# Schematic.net
KiCad netlist of a schematic drawn in EAGLE
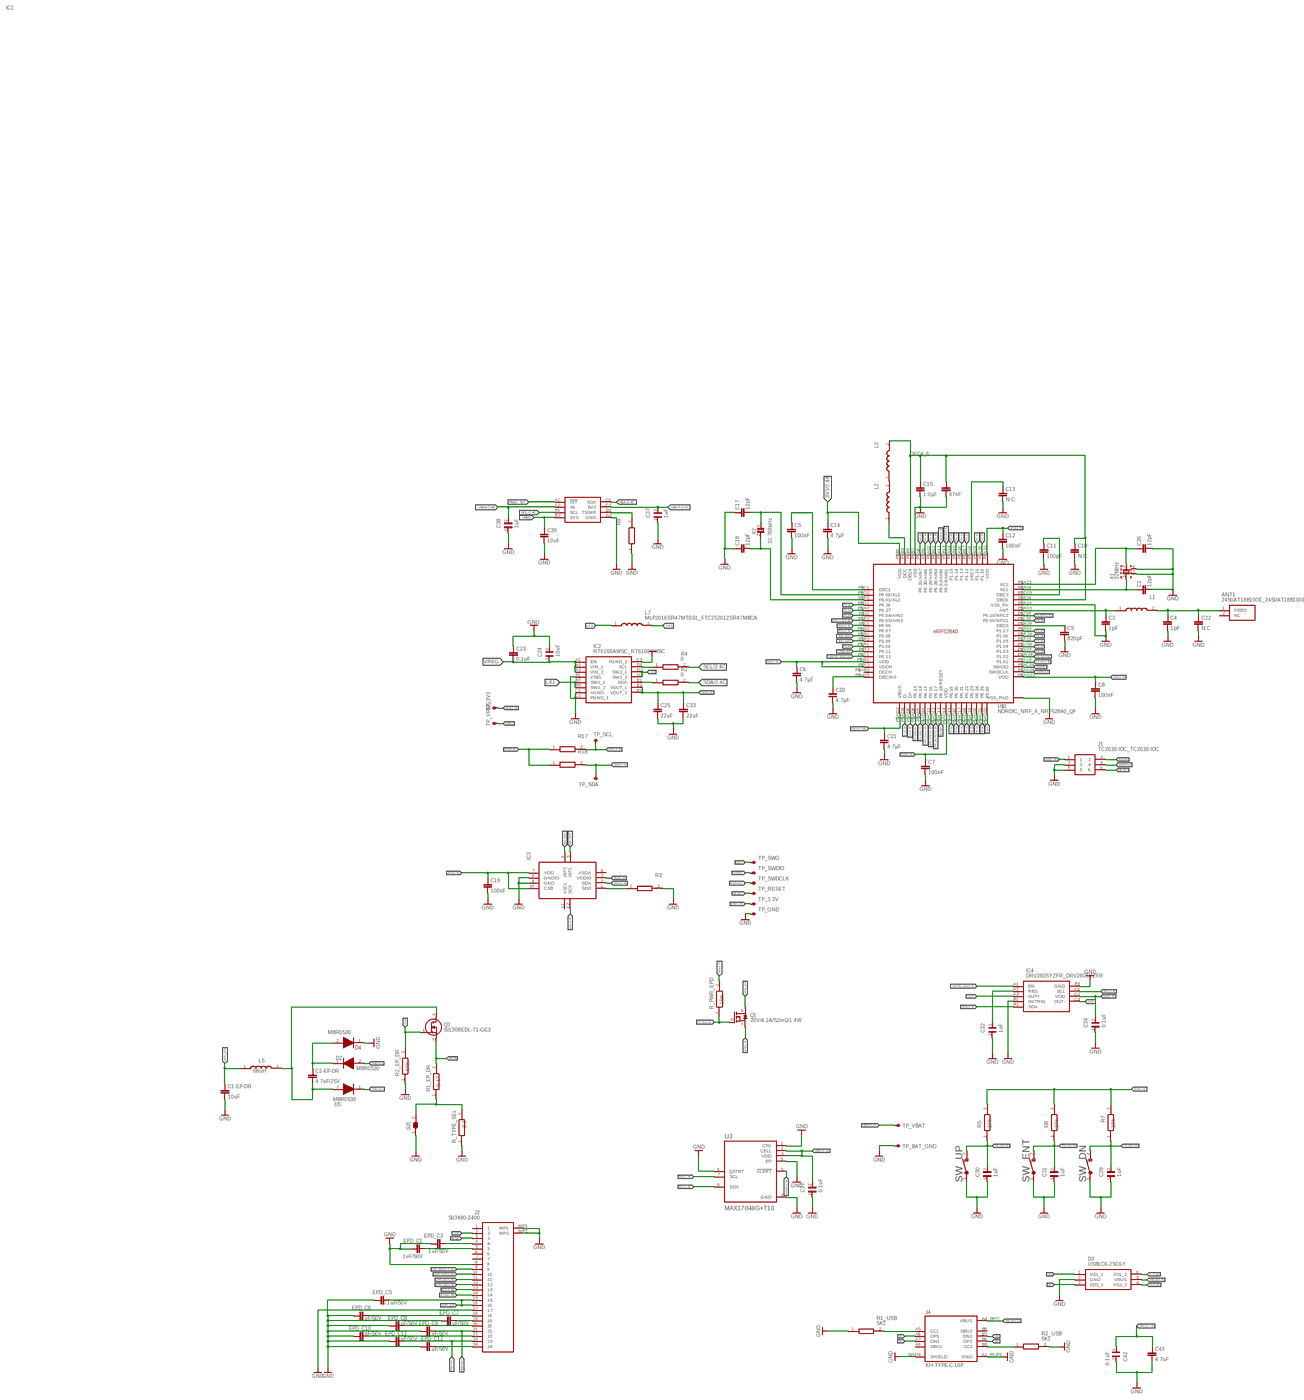
[diagram p0: schematic, sheet 1, overview]
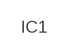
[diagram p1: schematic, sheet 1, part 1 of 4]
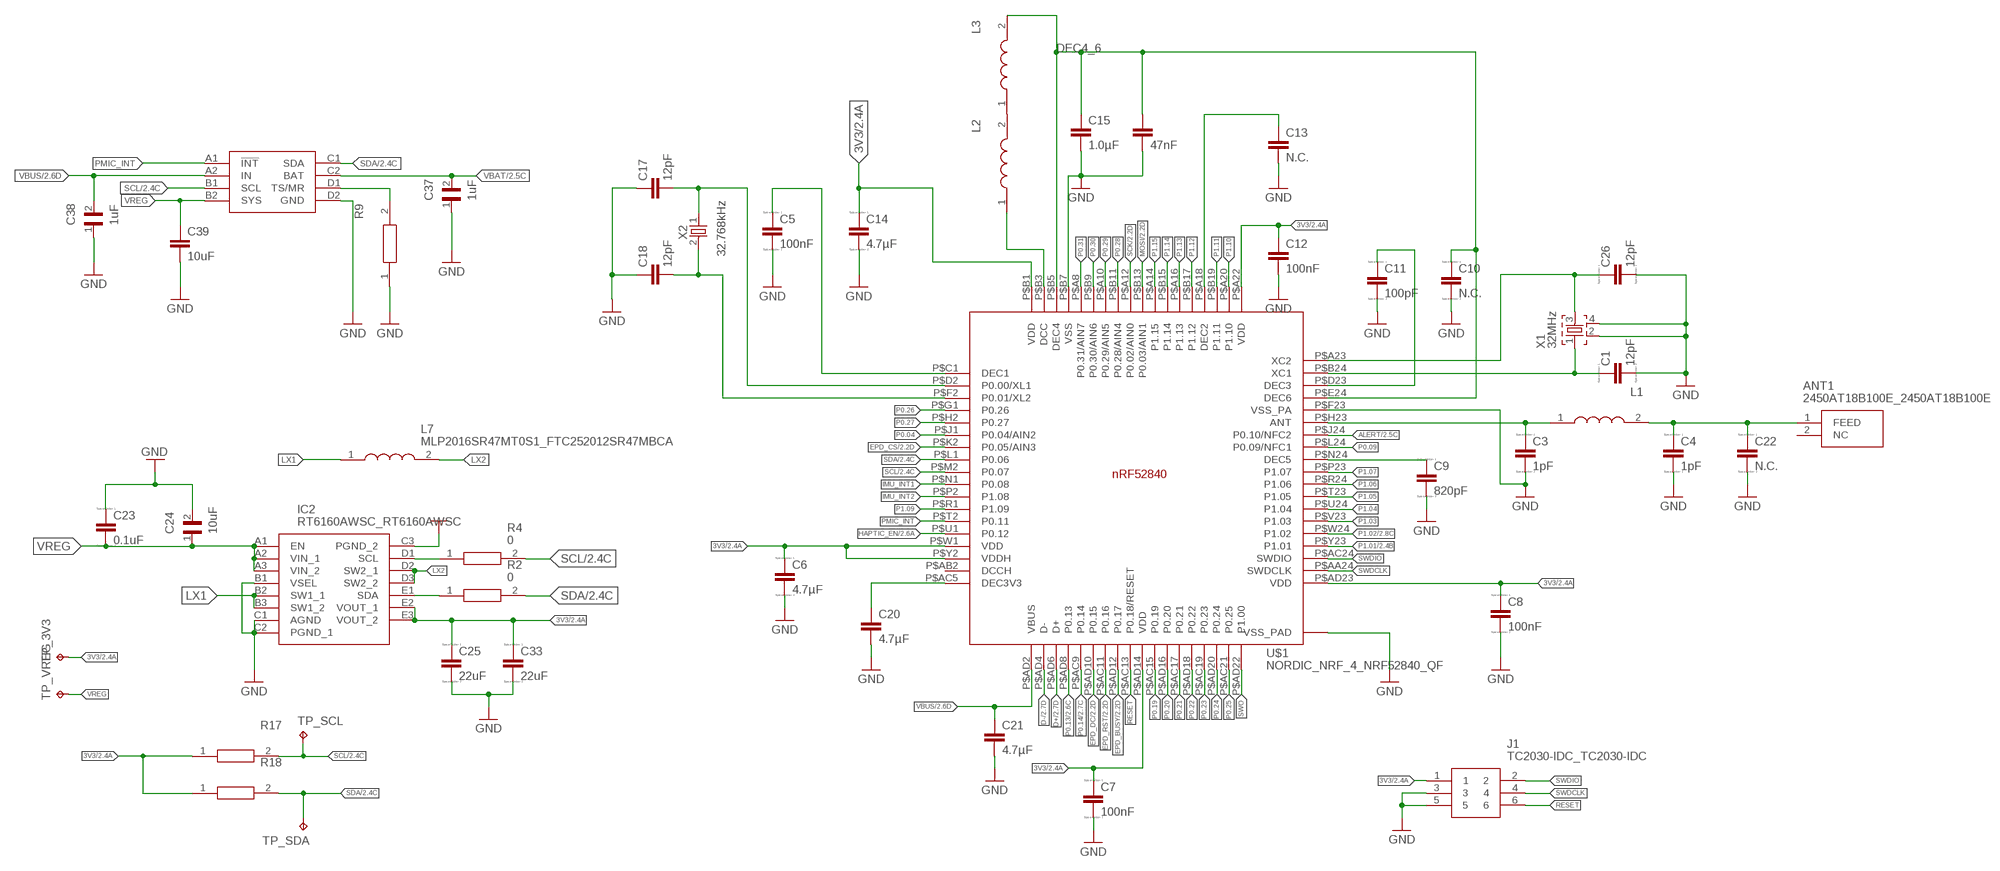
[diagram p2: schematic, sheet 1, part 2 of 4]
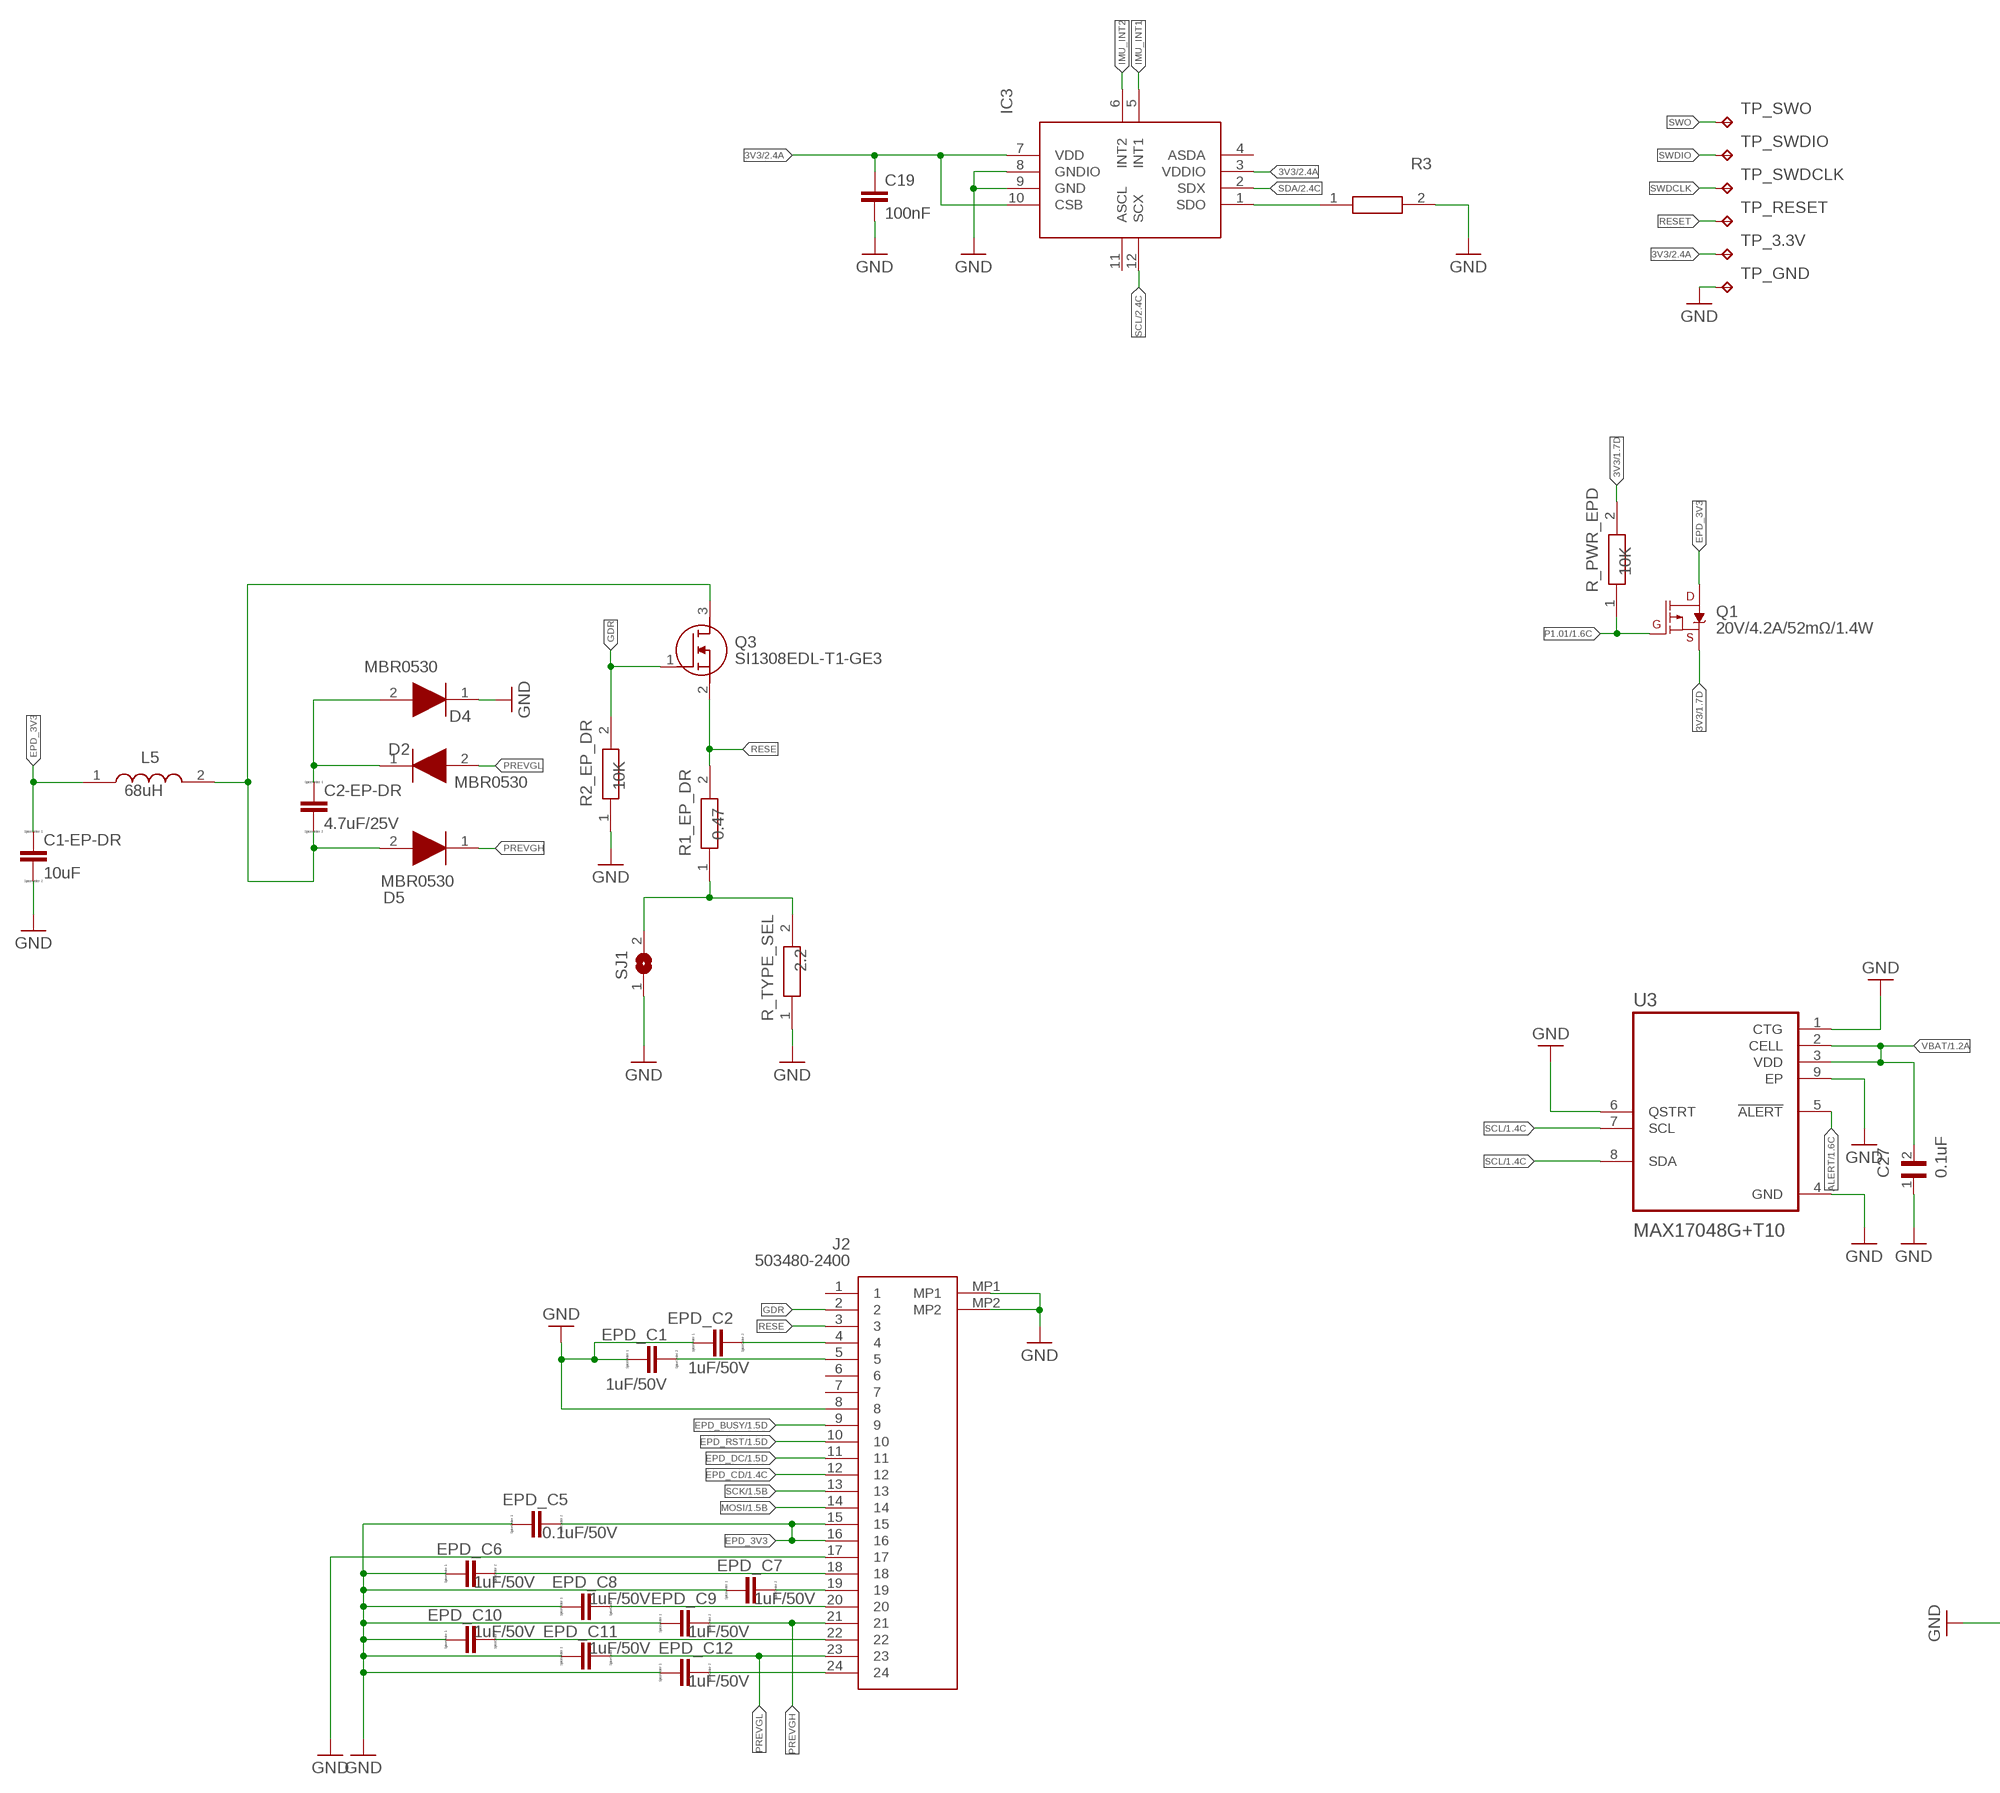
[diagram p3: schematic, sheet 1, part 3 of 4]
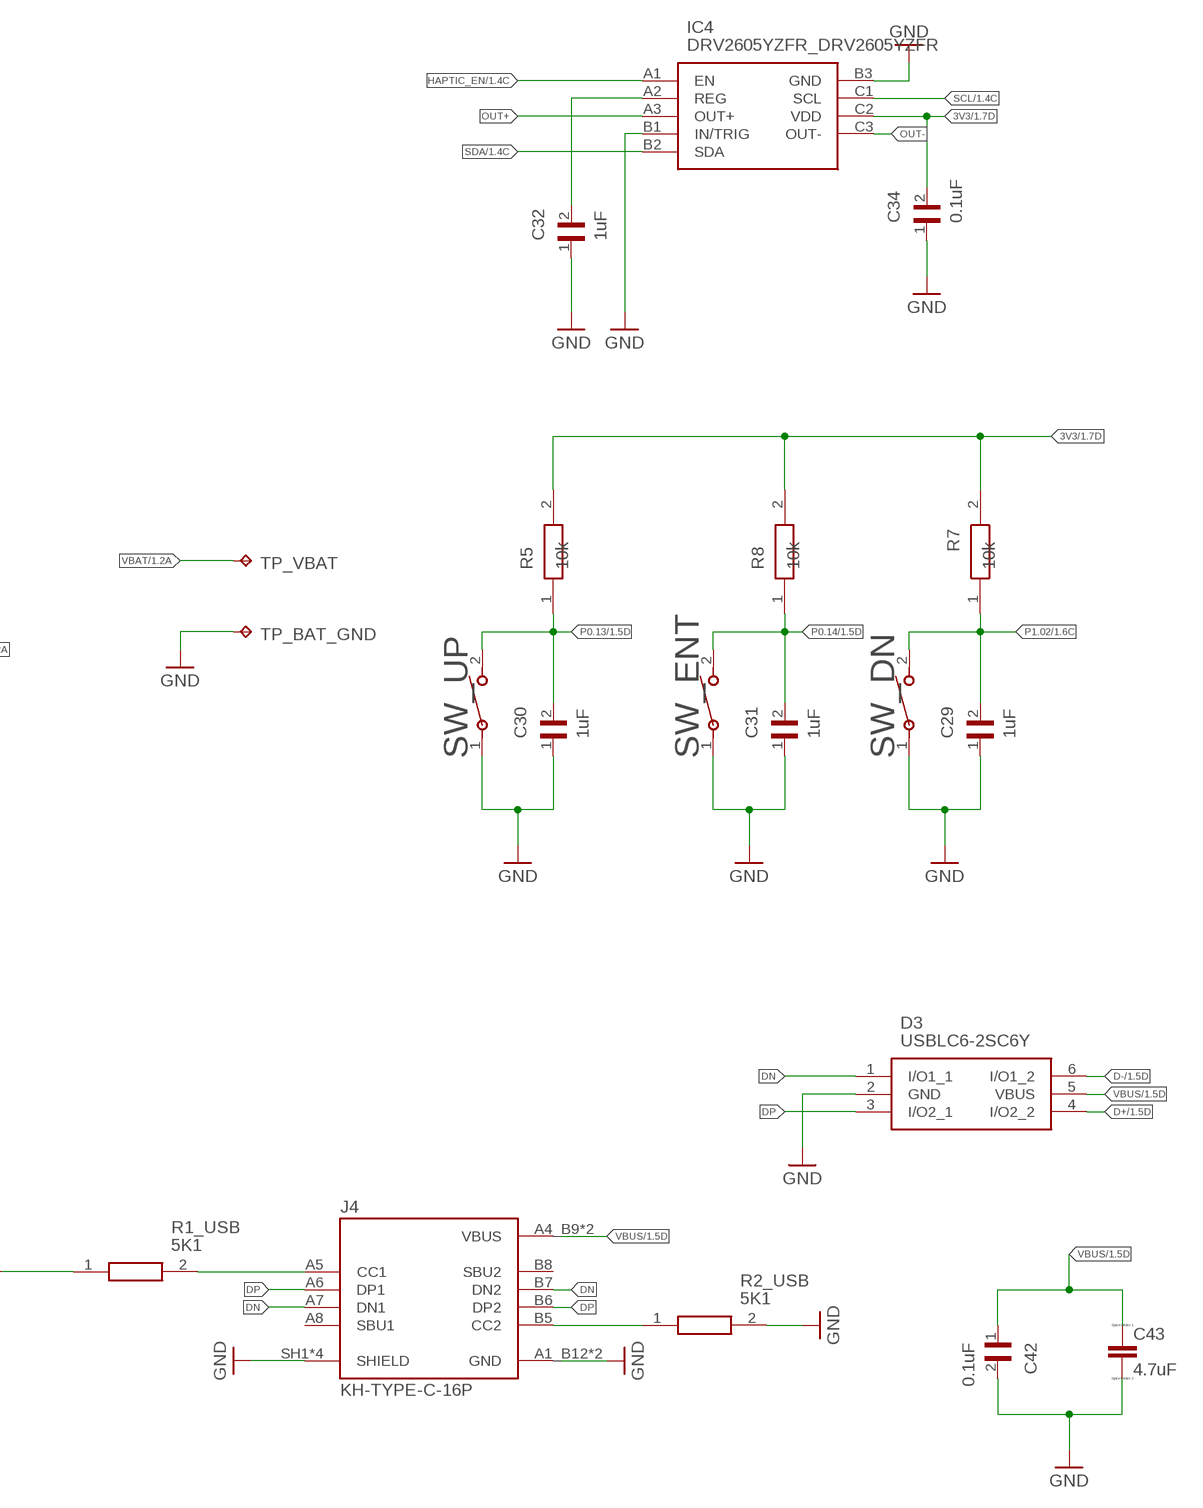
[diagram p4: schematic, sheet 1, part 4 of 4]

(export (version "E")
  (design (tool "Eeschema 10.0.6"))
  (components
    (comp (ref "ANT1")
      (value "2450AT18B100E_2450AT18B100E")
      (footprint "eagle-import:2450AT18B100E_ANTC3216X140N")
      (fields
        (field (name "ARROW_PART_NUMBER") "2450AT18B100E")
        (field (name "MOUSER_PART_NUMBER") "609-2450AT18B100E")
      )
      (libsource (lib "eagle-import") (part "2450AT18B100E_2450AT18B100E"))
    )
    (comp (ref "C1")
      (value "12pF")
      (footprint "eagle-import:ESP32_C6_LIBRARY_1_ESP32_WROVER_EAGLE-LTSPICE_C0402")
      (libsource (lib "eagle-import") (part "ESP32_C6_LIBRARY_1_ESP32_WROVER_EAGLE-LTSPICE_CC0402"))
    )
    (comp (ref "C1-EP-DR")
      (value "10uF")
      (footprint "eagle-import:ESP32_C6_LIBRARY_1_ESP32_WROVER_EAGLE-LTSPICE_C0402")
      (libsource (lib "eagle-import") (part "ESP32_C6_LIBRARY_1_ESP32_WROVER_EAGLE-LTSPICE_CC0402"))
    )
    (comp (ref "C2-EP-DR")
      (value "4.7uF/25V")
      (footprint "eagle-import:ESP32_C6_LIBRARY_1_ESP32_WROVER_EAGLE-LTSPICE_C0402")
      (libsource (lib "eagle-import") (part "ESP32_C6_LIBRARY_1_ESP32_WROVER_EAGLE-LTSPICE_CC0402"))
    )
    (comp (ref "C3")
      (value "1pF")
      (footprint "eagle-import:ESP32_C6_LIBRARY_1_ESP32_WROVER_EAGLE-LTSPICE_C0402")
      (libsource (lib "eagle-import") (part "ESP32_C6_LIBRARY_1_ESP32_WROVER_EAGLE-LTSPICE_CC0402"))
    )
    (comp (ref "C4")
      (value "1pF")
      (footprint "eagle-import:ESP32_C6_LIBRARY_1_ESP32_WROVER_EAGLE-LTSPICE_C0402")
      (libsource (lib "eagle-import") (part "ESP32_C6_LIBRARY_1_ESP32_WROVER_EAGLE-LTSPICE_CC0402"))
    )
    (comp (ref "C5")
      (value "100nF")
      (footprint "eagle-import:ESP32_C6_LIBRARY_1_ESP32_WROVER_EAGLE-LTSPICE_C0402")
      (libsource (lib "eagle-import") (part "ESP32_C6_LIBRARY_1_ESP32_WROVER_EAGLE-LTSPICE_CC0402"))
    )
    (comp (ref "C6")
      (value "4.7µF")
      (footprint "eagle-import:ESP32_C6_LIBRARY_1_ESP32_WROVER_EAGLE-LTSPICE_C0402")
      (libsource (lib "eagle-import") (part "ESP32_C6_LIBRARY_1_ESP32_WROVER_EAGLE-LTSPICE_CC0402"))
    )
    (comp (ref "C7")
      (value "100nF")
      (footprint "eagle-import:ESP32_C6_LIBRARY_1_ESP32_WROVER_EAGLE-LTSPICE_C0402")
      (libsource (lib "eagle-import") (part "ESP32_C6_LIBRARY_1_ESP32_WROVER_EAGLE-LTSPICE_CC0402"))
    )
    (comp (ref "C8")
      (value "100nF")
      (footprint "eagle-import:ESP32_C6_LIBRARY_1_ESP32_WROVER_EAGLE-LTSPICE_C0402")
      (libsource (lib "eagle-import") (part "ESP32_C6_LIBRARY_1_ESP32_WROVER_EAGLE-LTSPICE_CC0402"))
    )
    (comp (ref "C9")
      (value "820pF")
      (footprint "eagle-import:ESP32_C6_LIBRARY_1_ESP32_WROVER_EAGLE-LTSPICE_C0402")
      (libsource (lib "eagle-import") (part "ESP32_C6_LIBRARY_1_ESP32_WROVER_EAGLE-LTSPICE_CC0402"))
    )
    (comp (ref "C10")
      (value "N.C.")
      (footprint "eagle-import:ESP32_C6_LIBRARY_1_ESP32_WROVER_EAGLE-LTSPICE_C0402")
      (libsource (lib "eagle-import") (part "ESP32_C6_LIBRARY_1_ESP32_WROVER_EAGLE-LTSPICE_CC0402"))
    )
    (comp (ref "C11")
      (value "100pF")
      (footprint "eagle-import:ESP32_C6_LIBRARY_1_ESP32_WROVER_EAGLE-LTSPICE_C0402")
      (libsource (lib "eagle-import") (part "ESP32_C6_LIBRARY_1_ESP32_WROVER_EAGLE-LTSPICE_CC0402"))
    )
    (comp (ref "C12")
      (value "100nF")
      (footprint "eagle-import:PERFECT_0402_0402")
      (libsource (lib "eagle-import") (part "PERFECT_0402_CAP_0402"))
    )
    (comp (ref "C13")
      (value "N.C.")
      (footprint "eagle-import:PERFECT_0402_0402")
      (libsource (lib "eagle-import") (part "PERFECT_0402_CAP_0402"))
    )
    (comp (ref "C14")
      (value "4.7µF")
      (footprint "eagle-import:ESP32_C6_LIBRARY_1_ESP32_WROVER_EAGLE-LTSPICE_C0402")
      (libsource (lib "eagle-import") (part "ESP32_C6_LIBRARY_1_ESP32_WROVER_EAGLE-LTSPICE_CC0402"))
    )
    (comp (ref "C15")
      (value "1.0µF")
      (footprint "eagle-import:PERFECT_0402_0402")
      (libsource (lib "eagle-import") (part "PERFECT_0402_CAP_0402"))
    )
    (comp (ref "C16")
      (value "47nF")
      (footprint "eagle-import:PERFECT_0402_0402")
      (libsource (lib "eagle-import") (part "PERFECT_0402_CAP_0402"))
    )
    (comp (ref "C17")
      (value "12pF")
      (footprint "eagle-import:PERFECT_0402_0402")
      (libsource (lib "eagle-import") (part "PERFECT_0402_CAP_0402"))
    )
    (comp (ref "C18")
      (value "12pF")
      (footprint "eagle-import:PERFECT_0402_0402")
      (libsource (lib "eagle-import") (part "PERFECT_0402_CAP_0402"))
    )
    (comp (ref "C19")
      (value "100nF")
      (footprint "eagle-import:PERFECT_0402_0402")
      (libsource (lib "eagle-import") (part "PERFECT_0402_CAP_0402"))
    )
    (comp (ref "C20")
      (value "4.7µF")
      (footprint "eagle-import:PERFECT_0402_0402")
      (libsource (lib "eagle-import") (part "PERFECT_0402_CAP_0402"))
    )
    (comp (ref "C21")
      (value "4.7µF")
      (footprint "eagle-import:PERFECT_0402_0402")
      (libsource (lib "eagle-import") (part "PERFECT_0402_CAP_0402"))
    )
    (comp (ref "C22")
      (value "N.C.")
      (footprint "eagle-import:ESP32_C6_LIBRARY_1_ESP32_WROVER_EAGLE-LTSPICE_C0402")
      (libsource (lib "eagle-import") (part "ESP32_C6_LIBRARY_1_ESP32_WROVER_EAGLE-LTSPICE_CC0402"))
    )
    (comp (ref "C23")
      (value "0.1uF")
      (footprint "eagle-import:ESP32_C6_LIBRARY_1_ESP32_WROVER_EAGLE-LTSPICE_C0402")
      (libsource (lib "eagle-import") (part "ESP32_C6_LIBRARY_1_ESP32_WROVER_EAGLE-LTSPICE_CC0402"))
    )
    (comp (ref "C24")
      (value "10uF")
      (footprint "eagle-import:GRM011R60J152KE01L_2_CAPC0201X13N")
      (fields (field (name "MF") "Murata") (field (name "MP") "GRM011R60J152KE01L"))
      (libsource (lib "eagle-import") (part "GRM011R60J152KE01L_2_GRM011R60J152KE01L"))
    )
    (comp (ref "C25")
      (value "22uF")
      (footprint "eagle-import:ESP32_C6_LIBRARY_1_ESP32_WROVER_EAGLE-LTSPICE_C0402")
      (libsource (lib "eagle-import") (part "ESP32_C6_LIBRARY_1_ESP32_WROVER_EAGLE-LTSPICE_CC0402"))
    )
    (comp (ref "C26")
      (value "12pF")
      (footprint "eagle-import:ESP32_C6_LIBRARY_1_ESP32_WROVER_EAGLE-LTSPICE_C0402")
      (libsource (lib "eagle-import") (part "ESP32_C6_LIBRARY_1_ESP32_WROVER_EAGLE-LTSPICE_CC0402"))
    )
    (comp (ref "C27")
      (value "0.1uF")
      (footprint "eagle-import:GRM011R60J152KE01L_2_CAPC0201X13N")
      (fields (field (name "MF") "Murata") (field (name "MP") "GRM011R60J152KE01L"))
      (libsource (lib "eagle-import") (part "GRM011R60J152KE01L_2_GRM011R60J152KE01L"))
    )
    (comp (ref "C29")
      (value "1uF")
      (footprint "eagle-import:GRM011R60J152KE01L_2_CAPC0201X13N")
      (fields (field (name "MF") "Murata") (field (name "MP") "GRM011R60J152KE01L"))
      (libsource (lib "eagle-import") (part "GRM011R60J152KE01L_2_GRM011R60J152KE01L"))
    )
    (comp (ref "C30")
      (value "1uF")
      (footprint "eagle-import:GRM011R60J152KE01L_2_CAPC0201X13N")
      (fields (field (name "MF") "Murata") (field (name "MP") "GRM011R60J152KE01L"))
      (libsource (lib "eagle-import") (part "GRM011R60J152KE01L_2_GRM011R60J152KE01L"))
    )
    (comp (ref "C31")
      (value "1uF")
      (footprint "eagle-import:GRM011R60J152KE01L_2_CAPC0201X13N")
      (fields (field (name "MF") "Murata") (field (name "MP") "GRM011R60J152KE01L"))
      (libsource (lib "eagle-import") (part "GRM011R60J152KE01L_2_GRM011R60J152KE01L"))
    )
    (comp (ref "C32")
      (value "1uF")
      (footprint "eagle-import:GRM011R60J152KE01L_2_CAPC0201X13N")
      (fields (field (name "MF") "Murata") (field (name "MP") "GRM011R60J152KE01L"))
      (libsource (lib "eagle-import") (part "GRM011R60J152KE01L_2_GRM011R60J152KE01L"))
    )
    (comp (ref "C33")
      (value "22uF")
      (footprint "eagle-import:ESP32_C6_LIBRARY_1_ESP32_WROVER_EAGLE-LTSPICE_C0402")
      (libsource (lib "eagle-import") (part "ESP32_C6_LIBRARY_1_ESP32_WROVER_EAGLE-LTSPICE_CC0402"))
    )
    (comp (ref "C34")
      (value "0.1uF")
      (footprint "eagle-import:GRM011R60J152KE01L_2_CAPC0201X13N")
      (fields (field (name "MF") "Murata") (field (name "MP") "GRM011R60J152KE01L"))
      (libsource (lib "eagle-import") (part "GRM011R60J152KE01L_2_GRM011R60J152KE01L"))
    )
    (comp (ref "C37")
      (value "1uF")
      (footprint "eagle-import:GRM011R60J152KE01L_1_0201")
      (libsource (lib "eagle-import") (part "GRM011R60J152KE01L_1_GRM011R60J152KE01L"))
    )
    (comp (ref "C38")
      (value "1uF")
      (footprint "eagle-import:GRM011R60J152KE01L_1_0201")
      (libsource (lib "eagle-import") (part "GRM011R60J152KE01L_1_GRM011R60J152KE01L"))
    )
    (comp (ref "C39")
      (value "10uF")
      (footprint "eagle-import:PERFECT_0402_0402")
      (libsource (lib "eagle-import") (part "PERFECT_0402_CAP_0402"))
    )
    (comp (ref "C42")
      (value "0.1uF")
      (footprint "eagle-import:GRM011R60J152KE01L_2_CAPC0201X13N")
      (fields (field (name "MF") "Murata") (field (name "MP") "GRM011R60J152KE01L"))
      (libsource (lib "eagle-import") (part "GRM011R60J152KE01L_2_GRM011R60J152KE01L"))
    )
    (comp (ref "C43")
      (value "4.7uF")
      (footprint "eagle-import:ESP32_C6_LIBRARY_1_ESP32_WROVER_EAGLE-LTSPICE_C0402")
      (libsource (lib "eagle-import") (part "ESP32_C6_LIBRARY_1_ESP32_WROVER_EAGLE-LTSPICE_CC0402"))
    )
    (comp (ref "D2")
      (value "MBR0530")
      (footprint "eagle-import:ESP32_C6_LIBRARY_5_SOD3716X135N")
      (fields (field (name "MF") "ON Semiconductor"))
      (libsource (lib "eagle-import") (part "ESP32_C6_LIBRARY_5_MBR0530"))
    )
    (comp (ref "D3")
      (value "USBLC6-2SC6Y")
      (footprint "eagle-import:ESP32_C6_LIBRARY_3_SOT95P280X145-6N")
      (fields (field (name "MF") "STMicroelectronics"))
      (libsource (lib "eagle-import") (part "ESP32_C6_LIBRARY_3_USBLC6-2SC6Y"))
    )
    (comp (ref "D4")
      (value "MBR0530")
      (footprint "eagle-import:ESP32_C6_LIBRARY_5_SOD3716X135N")
      (fields (field (name "MF") "ON Semiconductor"))
      (libsource (lib "eagle-import") (part "ESP32_C6_LIBRARY_5_MBR0530"))
    )
    (comp (ref "D5")
      (value "MBR0530")
      (footprint "eagle-import:ESP32_C6_LIBRARY_5_SOD3716X135N")
      (fields (field (name "MF") "ON Semiconductor"))
      (libsource (lib "eagle-import") (part "ESP32_C6_LIBRARY_5_MBR0530"))
    )
    (comp (ref "EPD_C1")
      (value "1uF/50V")
      (footprint "eagle-import:ESP32_C6_LIBRARY_1_ESP32_WROVER_EAGLE-LTSPICE_C0402")
      (libsource (lib "eagle-import") (part "ESP32_C6_LIBRARY_1_ESP32_WROVER_EAGLE-LTSPICE_CC0402"))
    )
    (comp (ref "EPD_C2")
      (value "1uF/50V")
      (footprint "eagle-import:ESP32_C6_LIBRARY_1_ESP32_WROVER_EAGLE-LTSPICE_C0402")
      (libsource (lib "eagle-import") (part "ESP32_C6_LIBRARY_1_ESP32_WROVER_EAGLE-LTSPICE_CC0402"))
    )
    (comp (ref "EPD_C5")
      (value "0.1uF/50V")
      (footprint "eagle-import:ESP32_C6_LIBRARY_1_ESP32_WROVER_EAGLE-LTSPICE_C0402")
      (libsource (lib "eagle-import") (part "ESP32_C6_LIBRARY_1_ESP32_WROVER_EAGLE-LTSPICE_CC0402"))
    )
    (comp (ref "EPD_C6")
      (value "1uF/50V")
      (footprint "eagle-import:ESP32_C6_LIBRARY_1_ESP32_WROVER_EAGLE-LTSPICE_C0402")
      (libsource (lib "eagle-import") (part "ESP32_C6_LIBRARY_1_ESP32_WROVER_EAGLE-LTSPICE_CC0402"))
    )
    (comp (ref "EPD_C7")
      (value "1uF/50V")
      (footprint "eagle-import:ESP32_C6_LIBRARY_1_ESP32_WROVER_EAGLE-LTSPICE_C0402")
      (libsource (lib "eagle-import") (part "ESP32_C6_LIBRARY_1_ESP32_WROVER_EAGLE-LTSPICE_CC0402"))
    )
    (comp (ref "EPD_C8")
      (value "1uF/50V")
      (footprint "eagle-import:ESP32_C6_LIBRARY_1_ESP32_WROVER_EAGLE-LTSPICE_C0402")
      (libsource (lib "eagle-import") (part "ESP32_C6_LIBRARY_1_ESP32_WROVER_EAGLE-LTSPICE_CC0402"))
    )
    (comp (ref "EPD_C9")
      (value "1uF/50V")
      (footprint "eagle-import:ESP32_C6_LIBRARY_1_ESP32_WROVER_EAGLE-LTSPICE_C0402")
      (libsource (lib "eagle-import") (part "ESP32_C6_LIBRARY_1_ESP32_WROVER_EAGLE-LTSPICE_CC0402"))
    )
    (comp (ref "EPD_C10")
      (value "1uF/50V")
      (footprint "eagle-import:ESP32_C6_LIBRARY_1_ESP32_WROVER_EAGLE-LTSPICE_C0402")
      (libsource (lib "eagle-import") (part "ESP32_C6_LIBRARY_1_ESP32_WROVER_EAGLE-LTSPICE_CC0402"))
    )
    (comp (ref "EPD_C11")
      (value "1uF/50V")
      (footprint "eagle-import:ESP32_C6_LIBRARY_1_ESP32_WROVER_EAGLE-LTSPICE_C0402")
      (libsource (lib "eagle-import") (part "ESP32_C6_LIBRARY_1_ESP32_WROVER_EAGLE-LTSPICE_CC0402"))
    )
    (comp (ref "EPD_C12")
      (value "1uF/50V")
      (footprint "eagle-import:ESP32_C6_LIBRARY_1_ESP32_WROVER_EAGLE-LTSPICE_C0402")
      (libsource (lib "eagle-import") (part "ESP32_C6_LIBRARY_1_ESP32_WROVER_EAGLE-LTSPICE_CC0402"))
    )
    (comp (ref "IC1")
      (value "BQ25180YBGR_BQ25180YBGR")
      (footprint "eagle-import:BQ25180YBGR_BGA8C40P2X4_100X155X50")
      (fields
        (field (name "ARROW_PART_NUMBER") "BQ25180YBGR")
        (field (name "MOUSER_PART_NUMBER") "595-BQ25180YBGR")
      )
      (libsource (lib "eagle-import") (part "BQ25180YBGR_BQ25180YBGR"))
    )
    (comp (ref "IC2")
      (value "RT6160AWSC_RT6160AWSC")
      (footprint "eagle-import:RT6160AWSC_BGA15C40P3X5_140X230X60")
      (fields
        (field (name "MANUFACTURER_PART_NUMBER") "RT6160AWSC")
        (field (name "MOUSER_PART_NUMBER") "835-RT6160AWSC")
      )
      (libsource (lib "eagle-import") (part "RT6160AWSC_RT6160AWSC"))
    )
    (comp (ref "IC3")
      (value "BMA421_BMA421")
      (footprint "eagle-import:BMA421_BMA421")
      (fields (field (name "ARROW_PART_NUMBER") "BMA421") (field (name "MOUSER_PART_NUMBER") "262-BMA421"))
      (libsource (lib "eagle-import") (part "BMA421_BMA421"))
    )
    (comp (ref "IC4")
      (value "DRV2605YZFR_DRV2605YZFR")
      (footprint "eagle-import:DRV2605YZFR_BGA9C50P3X3_144X144X62")
      (fields (field (name "ARROW_PART_NUMBER") "DRV2605YZFR"))
      (libsource (lib "eagle-import") (part "DRV2605YZFR_DRV2605YZFR"))
    )
    (comp (ref "J1")
      (value "TC2030-IDC_TC2030-IDC")
      (footprint "eagle-import:TC2030-IDC_TC2030IDC")
      (fields (field (name "MANUFACTURER_PART_NUMBER") "TC2030-IDC"))
      (libsource (lib "eagle-import") (part "TC2030-IDC_TC2030-IDC"))
    )
    (comp (ref "J2")
      (value "503480-2400")
      (footprint "eagle-import:503480-2400_5034802400")
      (fields (field (name "MOUSER_PART_NUMBER") "538-503480-2400"))
      (libsource (lib "eagle-import") (part "503480-2400_503480-2400"))
    )
    (comp (ref "J4")
      (value "KH-TYPE-C-16P")
      (footprint "eagle-import:KH-TYPE-C-16P_KINGHELM_KH-TYPE-C-16P")
      (fields (field (name "MF") "kinghelm"))
      (libsource (lib "eagle-import") (part "KH-TYPE-C-16P_KH-TYPE-C-16P"))
    )
    (comp (ref "L1")
      (value "3.9nH")
      (footprint "eagle-import:MLP2016SR47MT0S1_INDC2016X100N")
      (fields (field (name "MANUFACTURER_PART_NUMBER") "FTC252012SR47MBCA"))
      (libsource (lib "eagle-import") (part "MLP2016SR47MT0S1_FTC252012SR47MBCA"))
    )
    (comp (ref "L2")
      (value "10µH")
      (footprint "eagle-import:MLP2016SR47MT0S1_INDC2016X100N")
      (fields (field (name "MANUFACTURER_PART_NUMBER") "FTC252012SR47MBCA"))
      (libsource (lib "eagle-import") (part "MLP2016SR47MT0S1_FTC252012SR47MBCA"))
    )
    (comp (ref "L3")
      (value "15nH")
      (footprint "eagle-import:MLP2016SR47MT0S1_INDC2016X100N")
      (fields (field (name "MANUFACTURER_PART_NUMBER") "FTC252012SR47MBCA"))
      (libsource (lib "eagle-import") (part "MLP2016SR47MT0S1_FTC252012SR47MBCA"))
    )
    (comp (ref "L5")
      (value "68uH")
      (footprint "eagle-import:MLP2016SR47MT0S1_INDC2016X100N")
      (fields (field (name "MANUFACTURER_PART_NUMBER") "FTC252012SR47MBCA"))
      (libsource (lib "eagle-import") (part "MLP2016SR47MT0S1_FTC252012SR47MBCA"))
    )
    (comp (ref "L7")
      (value "MLP2016SR47MT0S1_FTC252012SR47MBCA")
      (footprint "eagle-import:MLP2016SR47MT0S1_INDC2016X100N")
      (fields (field (name "MANUFACTURER_PART_NUMBER") "FTC252012SR47MBCA"))
      (libsource (lib "eagle-import") (part "MLP2016SR47MT0S1_FTC252012SR47MBCA"))
    )
    (comp (ref "Q1")
      (value "20V/4.2A/52mΩ/1.4W")
      (footprint "eagle-import:ESP32_C6_LIBRARY_4_ESP32_C6_LIBRARY_4_ESP32_C6_LIBRARY_4_ESP32_C6_LIBRARY_4_ESP32_WROVER_SPARKFUN-DISCRETESEMI_SOT23-3")
      (libsource (lib "eagle-import") (part "ESP32_C6_LIBRARY_4_ESP32_WROVER_SPARKFUN-DISCRETESEMI_MOSFET_PCH-DMG2305UX-7"))
    )
    (comp (ref "Q3")
      (value "SI1308EDL-T1-GE3")
      (footprint "eagle-import:ESP32_C6_LIBRARY_6_SOT65P210X110-3N")
      (fields (field (name "MF") "Vishay Siliconix"))
      (libsource (lib "eagle-import") (part "ESP32_C6_LIBRARY_6_SI1308EDL-T1-GE3"))
    )
    (comp (ref "R1_EP_DR")
      (value "0.47")
      (footprint "eagle-import:CPF0201D7K68C1_0201")
      (libsource (lib "eagle-import") (part "CPF0201D7K68C1_CPF0201D7K68C1"))
    )
    (comp (ref "R1_USB")
      (value "5K1")
      (footprint "eagle-import:ERA-1AEB3401C_0201")
      (libsource (lib "eagle-import") (part "ERA-1AEB3401C_CPF0201D7K68C1"))
    )
    (comp (ref "R2")
      (value "0")
      (footprint "eagle-import:CPF0201D7K68C1_0201")
      (libsource (lib "eagle-import") (part "CPF0201D7K68C1_CPF0201D7K68C1"))
    )
    (comp (ref "R2_EP_DR")
      (value "10K")
      (footprint "eagle-import:CPF0201D7K68C1_0201")
      (libsource (lib "eagle-import") (part "CPF0201D7K68C1_CPF0201D7K68C1"))
    )
    (comp (ref "R2_USB")
      (value "5K1")
      (footprint "eagle-import:ERA-1AEB3401C_0201")
      (libsource (lib "eagle-import") (part "ERA-1AEB3401C_CPF0201D7K68C1"))
    )
    (comp (ref "R3")
      (value "0")
      (footprint "eagle-import:CPF0201D7K68C1_0201")
      (libsource (lib "eagle-import") (part "CPF0201D7K68C1_CPF0201D7K68C1"))
    )
    (comp (ref "R4")
      (value "0")
      (footprint "eagle-import:CPF0201D7K68C1_0201")
      (libsource (lib "eagle-import") (part "CPF0201D7K68C1_CPF0201D7K68C1"))
    )
    (comp (ref "R5")
      (value "10k")
      (footprint "eagle-import:CPF0201D7K68C1_0201")
      (libsource (lib "eagle-import") (part "CPF0201D7K68C1_CPF0201D7K68C1"))
    )
    (comp (ref "R7")
      (value "10k")
      (footprint "eagle-import:CPF0201D7K68C1_0201")
      (libsource (lib "eagle-import") (part "CPF0201D7K68C1_CPF0201D7K68C1"))
    )
    (comp (ref "R8")
      (value "10k")
      (footprint "eagle-import:CPF0201D7K68C1_0201")
      (libsource (lib "eagle-import") (part "CPF0201D7K68C1_CPF0201D7K68C1"))
    )
    (comp (ref "R9")
      (value "10K")
      (footprint "eagle-import:CPF0201D7K68C1_0201")
      (libsource (lib "eagle-import") (part "CPF0201D7K68C1_CPF0201D7K68C1"))
    )
    (comp (ref "R17")
      (value "3K3")
      (footprint "eagle-import:CPF0201D7K68C1_0201")
      (libsource (lib "eagle-import") (part "CPF0201D7K68C1_CPF0201D7K68C1"))
    )
    (comp (ref "R18")
      (value "3K3")
      (footprint "eagle-import:CPF0201D7K68C1_0201")
      (libsource (lib "eagle-import") (part "CPF0201D7K68C1_CPF0201D7K68C1"))
    )
    (comp (ref "R_PWR_EPD")
      (value "10K")
      (footprint "eagle-import:CPF0201D7K68C1_0201")
      (libsource (lib "eagle-import") (part "CPF0201D7K68C1_CPF0201D7K68C1"))
    )
    (comp (ref "R_TYPE_SEL")
      (value "2.2")
      (footprint "eagle-import:CPF0201D7K68C1_0201")
      (libsource (lib "eagle-import") (part "CPF0201D7K68C1_CPF0201D7K68C1"))
    )
    (comp (ref "SJ1")
      (value "OPEN")
      (footprint "eagle-import:ESP32_C6_LIBRARY_7_JUMPER_SJ")
      (libsource (lib "eagle-import") (part "ESP32_C6_LIBRARY_7_JUMPER_SJ"))
    )
    (comp (ref "SW_DN")
      (value "2025-10-22_07-23-44_LIBRARY_EVP-AKE31ASW_EVP-AKE31A_PAN")
      (footprint "eagle-import:2025-10-22_07-23-44_LIBRARY_SW_EVP-AKE31A_PAN")
      (fields
        (field (name "MANUFACTURER_PART_NUMBER") "EVP-AKE31A")
        (field (name "COPYRIGHT") "Copyright (C) 2025 Ultra Librarian. All rights reserved.")
      )
      (libsource (lib "eagle-import") (part "2025-10-22_07-23-44_LIBRARY_EVP-AKE31ASW_EVP-AKE31A_PAN"))
    )
    (comp (ref "SW_ENT")
      (value "2025-10-22_07-23-44_LIBRARY_EVP-AKE31ASW_EVP-AKE31A_PAN")
      (footprint "eagle-import:2025-10-22_07-23-44_LIBRARY_SW_EVP-AKE31A_PAN")
      (fields
        (field (name "MANUFACTURER_PART_NUMBER") "EVP-AKE31A")
        (field (name "COPYRIGHT") "Copyright (C) 2025 Ultra Librarian. All rights reserved.")
      )
      (libsource (lib "eagle-import") (part "2025-10-22_07-23-44_LIBRARY_EVP-AKE31ASW_EVP-AKE31A_PAN"))
    )
    (comp (ref "SW_UP")
      (value "2025-10-22_07-23-44_LIBRARY_EVP-AKE31ASW_EVP-AKE31A_PAN")
      (footprint "eagle-import:2025-10-22_07-23-44_LIBRARY_SW_EVP-AKE31A_PAN")
      (fields
        (field (name "MANUFACTURER_PART_NUMBER") "EVP-AKE31A")
        (field (name "COPYRIGHT") "Copyright (C) 2025 Ultra Librarian. All rights reserved.")
      )
      (libsource (lib "eagle-import") (part "2025-10-22_07-23-44_LIBRARY_EVP-AKE31ASW_EVP-AKE31A_PAN"))
    )
    (comp (ref "TP_3.3V")
      (value "HECTOR_WATCH_1_TPTP20R")
      (footprint "eagle-import:HECTOR_WATCH_1_TP20R")
      (libsource (lib "eagle-import") (part "HECTOR_WATCH_1_TPTP20R"))
    )
    (comp (ref "TP_3V3")
      (value "HECTOR_WATCH_1_TPTP20R")
      (footprint "eagle-import:HECTOR_WATCH_1_TP20R")
      (libsource (lib "eagle-import") (part "HECTOR_WATCH_1_TPTP20R"))
    )
    (comp (ref "TP_BAT_GND")
      (value "HECTOR_WATCH_1_TPTP20R")
      (footprint "eagle-import:HECTOR_WATCH_1_TP20R")
      (libsource (lib "eagle-import") (part "HECTOR_WATCH_1_TPTP20R"))
    )
    (comp (ref "TP_GND")
      (value "HECTOR_WATCH_1_TPTP20R")
      (footprint "eagle-import:HECTOR_WATCH_1_TP20R")
      (libsource (lib "eagle-import") (part "HECTOR_WATCH_1_TPTP20R"))
    )
    (comp (ref "TP_RESET")
      (value "HECTOR_WATCH_1_TPTP20R")
      (footprint "eagle-import:HECTOR_WATCH_1_TP20R")
      (libsource (lib "eagle-import") (part "HECTOR_WATCH_1_TPTP20R"))
    )
    (comp (ref "TP_SCL")
      (value "HECTOR_WATCH_1_TPTP20R")
      (footprint "eagle-import:HECTOR_WATCH_1_TP20R")
      (libsource (lib "eagle-import") (part "HECTOR_WATCH_1_TPTP20R"))
    )
    (comp (ref "TP_SDA")
      (value "HECTOR_WATCH_1_TPTP20R")
      (footprint "eagle-import:HECTOR_WATCH_1_TP20R")
      (libsource (lib "eagle-import") (part "HECTOR_WATCH_1_TPTP20R"))
    )
    (comp (ref "TP_SWDCLK")
      (value "HECTOR_WATCH_1_TPTP20R")
      (footprint "eagle-import:HECTOR_WATCH_1_TP20R")
      (libsource (lib "eagle-import") (part "HECTOR_WATCH_1_TPTP20R"))
    )
    (comp (ref "TP_SWDIO")
      (value "HECTOR_WATCH_1_TPTP20R")
      (footprint "eagle-import:HECTOR_WATCH_1_TP20R")
      (libsource (lib "eagle-import") (part "HECTOR_WATCH_1_TPTP20R"))
    )
    (comp (ref "TP_SWO")
      (value "HECTOR_WATCH_1_TPTP20R")
      (footprint "eagle-import:HECTOR_WATCH_1_TP20R")
      (libsource (lib "eagle-import") (part "HECTOR_WATCH_1_TPTP20R"))
    )
    (comp (ref "TP_VBAT")
      (value "HECTOR_WATCH_1_TPTP20R")
      (footprint "eagle-import:HECTOR_WATCH_1_TP20R")
      (libsource (lib "eagle-import") (part "HECTOR_WATCH_1_TPTP20R"))
    )
    (comp (ref "TP_VREG")
      (value "HECTOR_WATCH_1_TPTP20R")
      (footprint "eagle-import:HECTOR_WATCH_1_TP20R")
      (libsource (lib "eagle-import") (part "HECTOR_WATCH_1_TPTP20R"))
    )
    (comp (ref "U$1")
      (value "NORDIC_NRF_4_NRF52840_QF")
      (footprint "eagle-import:NORDIC_NRF_4_AQFN50P700X700X85_HS-74N")
      (libsource (lib "eagle-import") (part "NORDIC_NRF_4_NRF52840_QF"))
    )
    (comp (ref "U3")
      (value "MAX17048G+T10")
      (footprint "eagle-import:ESP32_C6_LIBRARY_SON50P200X200X80-9N")
      (fields (field (name "MF") "Analog Devices"))
      (libsource (lib "eagle-import") (part "ESP32_C6_LIBRARY_MAX17048G+T10"))
    )
    (comp (ref "X1")
      (value "32MHz")
      (footprint "eagle-import:NORDIC_NRF_BT-XTAL_2016_N")
      (libsource (lib "eagle-import") (part "NORDIC_NRF_XTAL_32MHZ"))
    )
    (comp (ref "X2")
      (value "32.768kHz")
      (footprint "eagle-import:NORDIC_NRF_1_XTAL_3215_N")
      (libsource (lib "eagle-import") (part "NORDIC_NRF_1_XTAL_32KHZ"))
    )
  )
  (nets
    (net (code "1") (name "/DEC4_6") (class "Default")
      (node (ref "C10") (pin "1") (pinfunction "1_1") (pintype "passive"))
      (node (ref "C15") (pin "1") (pinfunction "1_1") (pintype "passive"))
      (node (ref "C16") (pin "1") (pinfunction "1_1") (pintype "passive"))
      (node (ref "L3") (pin "2") (pinfunction "2_2") (pintype "bidirectional"))
      (node (ref "U$1") (pin "P$B5") (pinfunction "DEC4_P$B5") (pintype "power_in"))
      (node (ref "U$1") (pin "P$E24") (pinfunction "DEC6_P$E24") (pintype "bidirectional"))
    )
    (net (code "2") (name "3V3{slash}1.7D") (class "Default")
      (node (ref "C34") (pin "2") (pinfunction "2_2") (pintype "passive"))
      (node (ref "IC4") (pin "C2") (pinfunction "VDD_C2") (pintype "bidirectional"))
      (node (ref "Q1") (pin "2") (pinfunction "S_2") (pintype "bidirectional"))
      (node (ref "R5") (pin "2") (pinfunction "2_2") (pintype "bidirectional"))
      (node (ref "R7") (pin "2") (pinfunction "2_2") (pintype "bidirectional"))
      (node (ref "R8") (pin "2") (pinfunction "2_2") (pintype "bidirectional"))
      (node (ref "R_PWR_EPD") (pin "2") (pinfunction "2_2") (pintype "bidirectional"))
    )
    (net (code "3") (name "3V3{slash}2.4A") (class "Default")
      (node (ref "C12") (pin "1") (pinfunction "1_1") (pintype "passive"))
      (node (ref "C14") (pin "1") (pinfunction "1_1") (pintype "passive"))
      (node (ref "C19") (pin "1") (pinfunction "1_1") (pintype "passive"))
      (node (ref "C25") (pin "1") (pinfunction "1_1") (pintype "passive"))
      (node (ref "C33") (pin "1") (pinfunction "1_1") (pintype "passive"))
      (node (ref "C6") (pin "1") (pinfunction "1_1") (pintype "passive"))
      (node (ref "C7") (pin "1") (pinfunction "1_1") (pintype "passive"))
      (node (ref "C8") (pin "1") (pinfunction "1_1") (pintype "passive"))
      (node (ref "IC2") (pin "E2") (pinfunction "VOUT_1_E2") (pintype "bidirectional"))
      (node (ref "IC2") (pin "E3") (pinfunction "VOUT_2_E3") (pintype "bidirectional"))
      (node (ref "IC3") (pin "10") (pinfunction "CSB_10") (pintype "bidirectional"))
      (node (ref "IC3") (pin "3") (pinfunction "VDDIO_3") (pintype "bidirectional"))
      (node (ref "IC3") (pin "7") (pinfunction "VDD_7") (pintype "bidirectional"))
      (node (ref "J1") (pin "1") (pinfunction "1_1") (pintype "bidirectional"))
      (node (ref "R17") (pin "1") (pinfunction "1_1") (pintype "bidirectional"))
      (node (ref "R18") (pin "1") (pinfunction "1_1") (pintype "bidirectional"))
      (node (ref "TP_3.3V") (pin "TP") (pinfunction "TP_TP") (pintype "input"))
      (node (ref "TP_3V3") (pin "TP") (pinfunction "TP_TP") (pintype "input"))
      (node (ref "U$1") (pin "P$A22") (pinfunction "VDD_P$A22") (pintype "power_in"))
      (node (ref "U$1") (pin "P$AD14") (pinfunction "VDD_P$AD14") (pintype "power_in"))
      (node (ref "U$1") (pin "P$AD23") (pinfunction "VDD_P$AD23") (pintype "power_in"))
      (node (ref "U$1") (pin "P$B1") (pinfunction "VDD_P$B1") (pintype "power_in"))
      (node (ref "U$1") (pin "P$W1") (pinfunction "VDD_P$W1") (pintype "power_in"))
      (node (ref "U$1") (pin "P$Y2") (pinfunction "VDDH_P$Y2") (pintype "power_in"))
    )
    (net (code "4") (name "ALERT{slash}1.6C") (class "Default")
      (node (ref "U3") (pin "5") (pinfunction "~{ALERT}_5") (pintype "output"))
    )
    (net (code "5") (name "ALERT{slash}2.5C") (class "Default")
      (node (ref "U$1") (pin "P$J24") (pinfunction "P0.10/NFC2_P$J24") (pintype "bidirectional"))
    )
    (net (code "6") (name "D+{slash}1.5D") (class "Default")
      (node (ref "D3") (pin "4") (pinfunction "I/O2_2_4") (pintype "bidirectional"))
    )
    (net (code "7") (name "D+{slash}2.7D") (class "Default")
      (node (ref "U$1") (pin "P$AD6") (pinfunction "D+_P$AD6") (pintype "bidirectional"))
    )
    (net (code "8") (name "D-{slash}1.5D") (class "Default")
      (node (ref "D3") (pin "6") (pinfunction "I/O1_2_6") (pintype "bidirectional"))
    )
    (net (code "9") (name "D-{slash}2.7D") (class "Default")
      (node (ref "U$1") (pin "P$AD4") (pinfunction "D-_P$AD4") (pintype "bidirectional"))
    )
    (net (code "10") (name "DN") (class "Default")
      (node (ref "D3") (pin "1") (pinfunction "I/O1_1_1") (pintype "bidirectional"))
      (node (ref "J4") (pin "A7") (pinfunction "DN1_A7") (pintype "bidirectional"))
      (node (ref "J4") (pin "B7") (pinfunction "DN2_B7") (pintype "bidirectional"))
    )
    (net (code "11") (name "DP") (class "Default")
      (node (ref "D3") (pin "3") (pinfunction "I/O2_1_3") (pintype "bidirectional"))
      (node (ref "J4") (pin "A6") (pinfunction "DP1_A6") (pintype "bidirectional"))
      (node (ref "J4") (pin "B6") (pinfunction "DP2_B6") (pintype "bidirectional"))
    )
    (net (code "12") (name "EPD_3V3") (class "Default")
      (node (ref "C1-EP-DR") (pin "1") (pinfunction "1_1") (pintype "passive"))
      (node (ref "EPD_C5") (pin "2") (pinfunction "2_2") (pintype "passive"))
      (node (ref "J2") (pin "15") (pinfunction "15_15") (pintype "bidirectional"))
      (node (ref "J2") (pin "16") (pinfunction "16_16") (pintype "bidirectional"))
      (node (ref "L5") (pin "1") (pinfunction "1_1") (pintype "bidirectional"))
      (node (ref "Q1") (pin "3") (pinfunction "D_3") (pintype "bidirectional"))
    )
    (net (code "13") (name "EPD_BUSY{slash}1.5D") (class "Default")
      (node (ref "J2") (pin "9") (pinfunction "9_9") (pintype "bidirectional"))
    )
    (net (code "14") (name "EPD_BUSY{slash}2.2D") (class "Default")
      (node (ref "U$1") (pin "P$AD12") (pinfunction "P0.17_P$AD12") (pintype "bidirectional"))
    )
    (net (code "15") (name "EPD_CD{slash}1.4C") (class "Default")
      (node (ref "J2") (pin "12") (pinfunction "12_12") (pintype "bidirectional"))
    )
    (net (code "16") (name "EPD_CS{slash}2.2D") (class "Default")
      (node (ref "U$1") (pin "P$K2") (pinfunction "P0.05/AIN3_P$K2") (pintype "bidirectional"))
    )
    (net (code "17") (name "EPD_DC{slash}1.5D") (class "Default")
      (node (ref "J2") (pin "11") (pinfunction "11_11") (pintype "bidirectional"))
    )
    (net (code "18") (name "EPD_DC{slash}2.2D") (class "Default")
      (node (ref "U$1") (pin "P$AD10") (pinfunction "P0.15_P$AD10") (pintype "bidirectional"))
    )
    (net (code "19") (name "EPD_RST{slash}1.5D") (class "Default")
      (node (ref "J2") (pin "10") (pinfunction "10_10") (pintype "bidirectional"))
    )
    (net (code "20") (name "EPD_RST{slash}2.2D") (class "Default")
      (node (ref "U$1") (pin "P$AC11") (pinfunction "P0.16_P$AC11") (pintype "bidirectional"))
    )
    (net (code "21") (name "GDR") (class "Default")
      (node (ref "J2") (pin "2") (pinfunction "2_2") (pintype "bidirectional"))
      (node (ref "Q3") (pin "1") (pinfunction "G_1") (pintype "bidirectional"))
      (node (ref "R2_EP_DR") (pin "2") (pinfunction "2_2") (pintype "bidirectional"))
    )
    (net (code "22") (name "GND") (class "Default")
      (node (ref "C1") (pin "2") (pinfunction "2_2") (pintype "passive"))
      (node (ref "C1-EP-DR") (pin "2") (pinfunction "2_2") (pintype "passive"))
      (node (ref "C10") (pin "2") (pinfunction "2_2") (pintype "passive"))
      (node (ref "C11") (pin "2") (pinfunction "2_2") (pintype "passive"))
      (node (ref "C12") (pin "2") (pinfunction "2_2") (pintype "passive"))
      (node (ref "C13") (pin "2") (pinfunction "2_2") (pintype "passive"))
      (node (ref "C14") (pin "2") (pinfunction "2_2") (pintype "passive"))
      (node (ref "C15") (pin "2") (pinfunction "2_2") (pintype "passive"))
      (node (ref "C16") (pin "2") (pinfunction "2_2") (pintype "passive"))
      (node (ref "C17") (pin "1") (pinfunction "1_1") (pintype "passive"))
      (node (ref "C18") (pin "1") (pinfunction "1_1") (pintype "passive"))
      (node (ref "C19") (pin "2") (pinfunction "2_2") (pintype "passive"))
      (node (ref "C20") (pin "2") (pinfunction "2_2") (pintype "passive"))
      (node (ref "C21") (pin "2") (pinfunction "2_2") (pintype "passive"))
      (node (ref "C22") (pin "2") (pinfunction "2_2") (pintype "passive"))
      (node (ref "C23") (pin "1") (pinfunction "1_1") (pintype "passive"))
      (node (ref "C24") (pin "2") (pinfunction "2_2") (pintype "passive"))
      (node (ref "C25") (pin "2") (pinfunction "2_2") (pintype "passive"))
      (node (ref "C26") (pin "2") (pinfunction "2_2") (pintype "passive"))
      (node (ref "C27") (pin "1") (pinfunction "1_1") (pintype "passive"))
      (node (ref "C29") (pin "1") (pinfunction "1_1") (pintype "passive"))
      (node (ref "C3") (pin "2") (pinfunction "2_2") (pintype "passive"))
      (node (ref "C30") (pin "1") (pinfunction "1_1") (pintype "passive"))
      (node (ref "C31") (pin "1") (pinfunction "1_1") (pintype "passive"))
      (node (ref "C32") (pin "1") (pinfunction "1_1") (pintype "passive"))
      (node (ref "C33") (pin "2") (pinfunction "2_2") (pintype "passive"))
      (node (ref "C34") (pin "1") (pinfunction "1_1") (pintype "passive"))
      (node (ref "C37") (pin "1") (pinfunction "1_1") (pintype "passive"))
      (node (ref "C38") (pin "1") (pinfunction "1_1") (pintype "passive"))
      (node (ref "C39") (pin "2") (pinfunction "2_2") (pintype "passive"))
      (node (ref "C4") (pin "2") (pinfunction "2_2") (pintype "passive"))
      (node (ref "C42") (pin "2") (pinfunction "2_2") (pintype "passive"))
      (node (ref "C43") (pin "2") (pinfunction "2_2") (pintype "passive"))
      (node (ref "C5") (pin "2") (pinfunction "2_2") (pintype "passive"))
      (node (ref "C6") (pin "2") (pinfunction "2_2") (pintype "passive"))
      (node (ref "C7") (pin "2") (pinfunction "2_2") (pintype "passive"))
      (node (ref "C8") (pin "2") (pinfunction "2_2") (pintype "passive"))
      (node (ref "C9") (pin "2") (pinfunction "2_2") (pintype "passive"))
      (node (ref "D3") (pin "2") (pinfunction "GND_2") (pintype "bidirectional"))
      (node (ref "D4") (pin "1") (pinfunction "K_1") (pintype "bidirectional"))
      (node (ref "EPD_C1") (pin "1") (pinfunction "1_1") (pintype "passive"))
      (node (ref "EPD_C10") (pin "1") (pinfunction "1_1") (pintype "passive"))
      (node (ref "EPD_C11") (pin "1") (pinfunction "1_1") (pintype "passive"))
      (node (ref "EPD_C12") (pin "1") (pinfunction "1_1") (pintype "passive"))
      (node (ref "EPD_C2") (pin "1") (pinfunction "1_1") (pintype "passive"))
      (node (ref "EPD_C5") (pin "1") (pinfunction "1_1") (pintype "passive"))
      (node (ref "EPD_C6") (pin "1") (pinfunction "1_1") (pintype "passive"))
      (node (ref "EPD_C7") (pin "1") (pinfunction "1_1") (pintype "passive"))
      (node (ref "EPD_C8") (pin "1") (pinfunction "1_1") (pintype "passive"))
      (node (ref "EPD_C9") (pin "1") (pinfunction "1_1") (pintype "passive"))
      (node (ref "IC1") (pin "D2") (pinfunction "GND_D2") (pintype "bidirectional"))
      (node (ref "IC2") (pin "B1") (pinfunction "VSEL_B1") (pintype "bidirectional"))
      (node (ref "IC2") (pin "C1") (pinfunction "AGND_C1") (pintype "bidirectional"))
      (node (ref "IC2") (pin "C2") (pinfunction "PGND_1_C2") (pintype "bidirectional"))
      (node (ref "IC2") (pin "C3") (pinfunction "PGND_2_C3") (pintype "bidirectional"))
      (node (ref "IC3") (pin "8") (pinfunction "GNDIO_8") (pintype "bidirectional"))
      (node (ref "IC3") (pin "9") (pinfunction "GND_9") (pintype "bidirectional"))
      (node (ref "IC4") (pin "B1") (pinfunction "IN/TRIG_B1") (pintype "bidirectional"))
      (node (ref "IC4") (pin "B3") (pinfunction "GND_B3") (pintype "bidirectional"))
      (node (ref "J1") (pin "3") (pinfunction "3_3") (pintype "bidirectional"))
      (node (ref "J1") (pin "5") (pinfunction "5_5") (pintype "bidirectional"))
      (node (ref "J2") (pin "17") (pinfunction "17_17") (pintype "bidirectional"))
      (node (ref "J2") (pin "8") (pinfunction "8_8") (pintype "bidirectional"))
      (node (ref "J2") (pin "MP1") (pinfunction "MP1_MP1") (pintype "bidirectional"))
      (node (ref "J2") (pin "MP2") (pinfunction "MP2_MP2") (pintype "bidirectional"))
      (node (ref "J4") (pin "A12_B1") (pinfunction "GND_A12_B1") (pintype "power_in"))
      (node (ref "J4") (pin "A1_B12") (pinfunction "GND_A1_B12") (pintype "power_in"))
      (node (ref "J4") (pin "SH1") (pinfunction "SHIELD_SH1") (pintype "passive"))
      (node (ref "J4") (pin "SH2") (pinfunction "SHIELD_SH2") (pintype "passive"))
      (node (ref "J4") (pin "SH3") (pinfunction "SHIELD_SH3") (pintype "passive"))
      (node (ref "J4") (pin "SH4") (pinfunction "SHIELD_SH4") (pintype "passive"))
      (node (ref "R1_USB") (pin "1") (pinfunction "1_1") (pintype "bidirectional"))
      (node (ref "R2_EP_DR") (pin "1") (pinfunction "1_1") (pintype "bidirectional"))
      (node (ref "R2_USB") (pin "2") (pinfunction "2_2") (pintype "bidirectional"))
      (node (ref "R3") (pin "2") (pinfunction "2_2") (pintype "bidirectional"))
      (node (ref "R9") (pin "1") (pinfunction "1_1") (pintype "bidirectional"))
      (node (ref "R_TYPE_SEL") (pin "1") (pinfunction "1_1") (pintype "bidirectional"))
      (node (ref "SJ1") (pin "1") (pinfunction "1_1") (pintype "passive"))
      (node (ref "SW_DN") (pin "1") (pinfunction "1_1") (pintype "passive"))
      (node (ref "SW_ENT") (pin "1") (pinfunction "1_1") (pintype "passive"))
      (node (ref "SW_UP") (pin "1") (pinfunction "1_1") (pintype "passive"))
      (node (ref "TP_BAT_GND") (pin "TP") (pinfunction "TP_TP") (pintype "input"))
      (node (ref "TP_GND") (pin "TP") (pinfunction "TP_TP") (pintype "input"))
      (node (ref "U$1") (pin "P$74") (pinfunction "VSS_PAD_P$74") (pintype "bidirectional"))
      (node (ref "U$1") (pin "P$75") (pinfunction "VSS_PAD_P$75") (pintype "bidirectional"))
      (node (ref "U$1") (pin "P$76") (pinfunction "VSS_PAD_P$76") (pintype "bidirectional"))
      (node (ref "U$1") (pin "P$77") (pinfunction "VSS_PAD_P$77") (pintype "bidirectional"))
      (node (ref "U$1") (pin "P$78") (pinfunction "VSS_PAD_P$78") (pintype "bidirectional"))
      (node (ref "U$1") (pin "P$79") (pinfunction "VSS_PAD_P$79") (pintype "bidirectional"))
      (node (ref "U$1") (pin "P$80") (pinfunction "VSS_PAD_P$80") (pintype "bidirectional"))
      (node (ref "U$1") (pin "P$81") (pinfunction "VSS_PAD_P$81") (pintype "bidirectional"))
      (node (ref "U$1") (pin "P$82") (pinfunction "VSS_PAD_P$82") (pintype "bidirectional"))
      (node (ref "U$1") (pin "P$83") (pinfunction "VSS_PAD_P$83") (pintype "bidirectional"))
      (node (ref "U$1") (pin "P$84") (pinfunction "VSS_PAD_P$84") (pintype "bidirectional"))
      (node (ref "U$1") (pin "P$85") (pinfunction "VSS_PAD_P$85") (pintype "bidirectional"))
      (node (ref "U$1") (pin "P$86") (pinfunction "VSS_PAD_P$86") (pintype "bidirectional"))
      (node (ref "U$1") (pin "P$87") (pinfunction "VSS_PAD_P$87") (pintype "bidirectional"))
      (node (ref "U$1") (pin "P$88") (pinfunction "VSS_PAD_P$88") (pintype "bidirectional"))
      (node (ref "U$1") (pin "P$89") (pinfunction "VSS_PAD_P$89") (pintype "bidirectional"))
      (node (ref "U$1") (pin "P$90") (pinfunction "VSS_PAD_P$90") (pintype "bidirectional"))
      (node (ref "U$1") (pin "P$B7") (pinfunction "VSS_P$B7") (pintype "power_in"))
      (node (ref "U$1") (pin "P$F23") (pinfunction "VSS_PA_P$F23") (pintype "bidirectional"))
      (node (ref "U3") (pin "1") (pinfunction "CTG_1") (pintype "power_in"))
      (node (ref "U3") (pin "4") (pinfunction "GND_4") (pintype "power_in"))
      (node (ref "U3") (pin "6") (pinfunction "QSTRT_6") (pintype "input"))
      (node (ref "U3") (pin "9") (pinfunction "EP_9") (pintype "power_in"))
      (node (ref "X1") (pin "2") (pinfunction "2_2") (pintype "passive"))
      (node (ref "X1") (pin "4") (pinfunction "4_4") (pintype "passive"))
    )
    (net (code "23") (name "HAPTIC_EN{slash}1.4C") (class "Default")
      (node (ref "IC4") (pin "A1") (pinfunction "EN_A1") (pintype "bidirectional"))
    )
    (net (code "24") (name "HAPTIC_EN{slash}2.6A") (class "Default")
      (node (ref "U$1") (pin "P$U1") (pinfunction "P0.12_P$U1") (pintype "bidirectional"))
    )
    (net (code "25") (name "IMU_INT1") (class "Default")
      (node (ref "IC3") (pin "5") (pinfunction "INT1_5") (pintype "bidirectional"))
      (node (ref "U$1") (pin "P$N1") (pinfunction "P0.08_P$N1") (pintype "bidirectional"))
    )
    (net (code "26") (name "IMU_INT2") (class "Default")
      (node (ref "IC3") (pin "6") (pinfunction "INT2_6") (pintype "bidirectional"))
      (node (ref "U$1") (pin "P$P2") (pinfunction "P1.08_P$P2") (pintype "bidirectional"))
    )
    (net (code "27") (name "LX1") (class "Default")
      (node (ref "IC2") (pin "B2") (pinfunction "SW1_1_B2") (pintype "bidirectional"))
      (node (ref "IC2") (pin "B3") (pinfunction "SW1_2_B3") (pintype "bidirectional"))
      (node (ref "L7") (pin "1") (pinfunction "1_1") (pintype "bidirectional"))
    )
    (net (code "28") (name "LX2") (class "Default")
      (node (ref "IC2") (pin "D2") (pinfunction "SW2_1_D2") (pintype "bidirectional"))
      (node (ref "IC2") (pin "D3") (pinfunction "SW2_2_D3") (pintype "bidirectional"))
      (node (ref "L7") (pin "2") (pinfunction "2_2") (pintype "bidirectional"))
    )
    (net (code "29") (name "MOSI{slash}1.5B") (class "Default")
      (node (ref "J2") (pin "14") (pinfunction "14_14") (pintype "bidirectional"))
    )
    (net (code "30") (name "MOSI{slash}2.2D") (class "Default")
      (node (ref "U$1") (pin "P$B13") (pinfunction "P0.03/AIN1_P$B13") (pintype "bidirectional"))
    )
    (net (code "31") (name "Net-(ANT1-FEED)") (class "Default")
      (node (ref "ANT1") (pin "1") (pinfunction "FEED_1") (pintype "input"))
      (node (ref "C22") (pin "1") (pinfunction "1_1") (pintype "passive"))
      (node (ref "C4") (pin "1") (pinfunction "1_1") (pintype "passive"))
      (node (ref "L1") (pin "2") (pinfunction "2_2") (pintype "bidirectional"))
    )
    (net (code "32") (name "Net-(D2-K)") (class "Default")
      (node (ref "C2-EP-DR") (pin "1") (pinfunction "1_1") (pintype "passive"))
      (node (ref "D2") (pin "1") (pinfunction "K_1") (pintype "bidirectional"))
      (node (ref "D4") (pin "2") (pinfunction "A_2") (pintype "bidirectional"))
    )
    (net (code "33") (name "Net-(D5-A)") (class "Default")
      (node (ref "C2-EP-DR") (pin "2") (pinfunction "2_2") (pintype "passive"))
      (node (ref "D5") (pin "2") (pinfunction "A_2") (pintype "bidirectional"))
      (node (ref "L5") (pin "2") (pinfunction "2_2") (pintype "bidirectional"))
      (node (ref "Q3") (pin "3") (pinfunction "D_3") (pintype "bidirectional"))
    )
    (net (code "34") (name "Net-(EPD_C1-Pad2)") (class "Default")
      (node (ref "EPD_C1") (pin "2") (pinfunction "2_2") (pintype "passive"))
      (node (ref "J2") (pin "5") (pinfunction "5_5") (pintype "bidirectional"))
    )
    (net (code "35") (name "Net-(EPD_C2-Pad2)") (class "Default")
      (node (ref "EPD_C2") (pin "2") (pinfunction "2_2") (pintype "passive"))
      (node (ref "J2") (pin "4") (pinfunction "4_4") (pintype "bidirectional"))
    )
    (net (code "36") (name "Net-(EPD_C6-Pad2)") (class "Default")
      (node (ref "EPD_C6") (pin "2") (pinfunction "2_2") (pintype "passive"))
      (node (ref "J2") (pin "18") (pinfunction "18_18") (pintype "bidirectional"))
    )
    (net (code "37") (name "Net-(EPD_C7-Pad2)") (class "Default")
      (node (ref "EPD_C7") (pin "2") (pinfunction "2_2") (pintype "passive"))
      (node (ref "J2") (pin "19") (pinfunction "19_19") (pintype "bidirectional"))
    )
    (net (code "38") (name "Net-(EPD_C8-Pad2)") (class "Default")
      (node (ref "EPD_C8") (pin "2") (pinfunction "2_2") (pintype "passive"))
      (node (ref "J2") (pin "20") (pinfunction "20_20") (pintype "bidirectional"))
    )
    (net (code "39") (name "Net-(EPD_C10-Pad2)") (class "Default")
      (node (ref "EPD_C10") (pin "2") (pinfunction "2_2") (pintype "passive"))
      (node (ref "J2") (pin "22") (pinfunction "22_22") (pintype "bidirectional"))
    )
    (net (code "40") (name "Net-(EPD_C12-Pad2)") (class "Default")
      (node (ref "EPD_C12") (pin "2") (pinfunction "2_2") (pintype "passive"))
      (node (ref "J2") (pin "24") (pinfunction "24_24") (pintype "bidirectional"))
    )
    (net (code "41") (name "Net-(IC1-TS{slash}MR)") (class "Default")
      (node (ref "IC1") (pin "D1") (pinfunction "TS/MR_D1") (pintype "bidirectional"))
      (node (ref "R9") (pin "2") (pinfunction "2_2") (pintype "bidirectional"))
    )
    (net (code "42") (name "Net-(IC2-SCL)") (class "Default")
      (node (ref "IC2") (pin "D1") (pinfunction "SCL_D1") (pintype "bidirectional"))
      (node (ref "R4") (pin "1") (pinfunction "1_1") (pintype "bidirectional"))
    )
    (net (code "43") (name "Net-(IC2-SDA)") (class "Default")
      (node (ref "IC2") (pin "E1") (pinfunction "SDA_E1") (pintype "bidirectional"))
      (node (ref "R2") (pin "1") (pinfunction "1_1") (pintype "bidirectional"))
    )
    (net (code "44") (name "Net-(IC3-SDO)") (class "Default")
      (node (ref "IC3") (pin "1") (pinfunction "SDO_1") (pintype "bidirectional"))
      (node (ref "R3") (pin "1") (pinfunction "1_1") (pintype "bidirectional"))
    )
    (net (code "45") (name "Net-(IC4-REG)") (class "Default")
      (node (ref "C32") (pin "2") (pinfunction "2_2") (pintype "passive"))
      (node (ref "IC4") (pin "A2") (pinfunction "REG_A2") (pintype "bidirectional"))
    )
    (net (code "46") (name "Net-(J4-CC1)") (class "Default")
      (node (ref "J4") (pin "A5") (pinfunction "CC1_A5") (pintype "bidirectional"))
      (node (ref "R1_USB") (pin "2") (pinfunction "2_2") (pintype "bidirectional"))
    )
    (net (code "47") (name "Net-(J4-CC2)") (class "Default")
      (node (ref "J4") (pin "B5") (pinfunction "CC2_B5") (pintype "bidirectional"))
      (node (ref "R2_USB") (pin "1") (pinfunction "1_1") (pintype "bidirectional"))
    )
    (net (code "48") (name "Net-(L2-Pad2)") (class "Default")
      (node (ref "L2") (pin "2") (pinfunction "2_2") (pintype "bidirectional"))
      (node (ref "L3") (pin "1") (pinfunction "1_1") (pintype "bidirectional"))
    )
    (net (code "49") (name "Net-(R1_EP_DR-Pad1)") (class "Default")
      (node (ref "R1_EP_DR") (pin "1") (pinfunction "1_1") (pintype "bidirectional"))
      (node (ref "R_TYPE_SEL") (pin "2") (pinfunction "2_2") (pintype "bidirectional"))
      (node (ref "SJ1") (pin "2") (pinfunction "2_2") (pintype "passive"))
    )
    (net (code "50") (name "Net-(U$1-ANT)") (class "Default")
      (node (ref "C3") (pin "1") (pinfunction "1_1") (pintype "passive"))
      (node (ref "L1") (pin "1") (pinfunction "1_1") (pintype "bidirectional"))
      (node (ref "U$1") (pin "P$H23") (pinfunction "ANT_P$H23") (pintype "bidirectional"))
    )
    (net (code "51") (name "Net-(U$1-DCC)") (class "Default")
      (node (ref "L2") (pin "1") (pinfunction "1_1") (pintype "bidirectional"))
      (node (ref "U$1") (pin "P$B3") (pinfunction "DCC_P$B3") (pintype "output"))
    )
    (net (code "52") (name "Net-(U$1-DEC1)") (class "Default")
      (node (ref "C5") (pin "1") (pinfunction "1_1") (pintype "passive"))
      (node (ref "U$1") (pin "P$C1") (pinfunction "DEC1_P$C1") (pintype "power_in"))
    )
    (net (code "53") (name "Net-(U$1-DEC2)") (class "Default")
      (node (ref "C13") (pin "1") (pinfunction "1_1") (pintype "passive"))
      (node (ref "U$1") (pin "P$A18") (pinfunction "DEC2_P$A18") (pintype "bidirectional"))
    )
    (net (code "54") (name "Net-(U$1-DEC3)") (class "Default")
      (node (ref "C11") (pin "1") (pinfunction "1_1") (pintype "passive"))
      (node (ref "U$1") (pin "P$D23") (pinfunction "DEC3_P$D23") (pintype "bidirectional"))
    )
    (net (code "55") (name "Net-(U$1-DEC3V3)") (class "Default")
      (node (ref "C20") (pin "1") (pinfunction "1_1") (pintype "passive"))
      (node (ref "U$1") (pin "P$AC5") (pinfunction "DEC3V3_P$AC5") (pintype "bidirectional"))
    )
    (net (code "56") (name "Net-(U$1-DEC5)") (class "Default")
      (node (ref "C9") (pin "1") (pinfunction "1_1") (pintype "passive"))
      (node (ref "U$1") (pin "P$N24") (pinfunction "DEC5_P$N24") (pintype "bidirectional"))
    )
    (net (code "57") (name "Net-(U$1-P0.00{slash}XL1)") (class "Default")
      (node (ref "C17") (pin "2") (pinfunction "2_2") (pintype "passive"))
      (node (ref "U$1") (pin "P$D2") (pinfunction "P0.00/XL1_P$D2") (pintype "bidirectional"))
      (node (ref "X2") (pin "1") (pinfunction "1_1") (pintype "passive"))
    )
    (net (code "58") (name "Net-(U$1-P0.01{slash}XL2)") (class "Default")
      (node (ref "C18") (pin "2") (pinfunction "2_2") (pintype "passive"))
      (node (ref "U$1") (pin "P$F2") (pinfunction "P0.01/XL2_P$F2") (pintype "bidirectional"))
      (node (ref "X2") (pin "2") (pinfunction "2_2") (pintype "passive"))
    )
    (net (code "59") (name "Net-(U$1-XC1)") (class "Default")
      (node (ref "C1") (pin "1") (pinfunction "1_1") (pintype "passive"))
      (node (ref "U$1") (pin "P$B24") (pinfunction "XC1_P$B24") (pintype "input"))
      (node (ref "X1") (pin "1") (pinfunction "1_1") (pintype "passive"))
    )
    (net (code "60") (name "Net-(U$1-XC2)") (class "Default")
      (node (ref "C26") (pin "1") (pinfunction "1_1") (pintype "passive"))
      (node (ref "U$1") (pin "P$A23") (pinfunction "XC2_P$A23") (pintype "output"))
      (node (ref "X1") (pin "3") (pinfunction "3_3") (pintype "passive"))
    )
    (net (code "61") (name "OUT+") (class "Default")
      (node (ref "IC4") (pin "A3") (pinfunction "OUT+_A3") (pintype "bidirectional"))
    )
    (net (code "62") (name "OUT-") (class "Default")
      (node (ref "IC4") (pin "C3") (pinfunction "OUT-_C3") (pintype "bidirectional"))
    )
    (net (code "63") (name "P0.04") (class "Default")
      (node (ref "U$1") (pin "P$J1") (pinfunction "P0.04/AIN2_P$J1") (pintype "bidirectional"))
    )
    (net (code "64") (name "P0.09") (class "Default")
      (node (ref "U$1") (pin "P$L24") (pinfunction "P0.09/NFC1_P$L24") (pintype "bidirectional"))
    )
    (net (code "65") (name "P0.13{slash}1.5D") (class "Default")
      (node (ref "C30") (pin "2") (pinfunction "2_2") (pintype "passive"))
      (node (ref "R5") (pin "1") (pinfunction "1_1") (pintype "bidirectional"))
      (node (ref "SW_UP") (pin "2") (pinfunction "2_2") (pintype "passive"))
    )
    (net (code "66") (name "P0.13{slash}2.6C") (class "Default")
      (node (ref "U$1") (pin "P$AD8") (pinfunction "P0.13_P$AD8") (pintype "bidirectional"))
    )
    (net (code "67") (name "P0.14{slash}1.5D") (class "Default")
      (node (ref "C31") (pin "2") (pinfunction "2_2") (pintype "passive"))
      (node (ref "R8") (pin "1") (pinfunction "1_1") (pintype "bidirectional"))
      (node (ref "SW_ENT") (pin "2") (pinfunction "2_2") (pintype "passive"))
    )
    (net (code "68") (name "P0.14{slash}2.7C") (class "Default")
      (node (ref "U$1") (pin "P$AC9") (pinfunction "P0.14_P$AC9") (pintype "bidirectional"))
    )
    (net (code "69") (name "P0.19") (class "Default")
      (node (ref "U$1") (pin "P$AC15") (pinfunction "P0.19_P$AC15") (pintype "bidirectional"))
    )
    (net (code "70") (name "P0.20") (class "Default")
      (node (ref "U$1") (pin "P$AD16") (pinfunction "P0.20_P$AD16") (pintype "bidirectional"))
    )
    (net (code "71") (name "P0.21") (class "Default")
      (node (ref "U$1") (pin "P$AC17") (pinfunction "P0.21_P$AC17") (pintype "bidirectional"))
    )
    (net (code "72") (name "P0.22") (class "Default")
      (node (ref "U$1") (pin "P$AD18") (pinfunction "P0.22_P$AD18") (pintype "bidirectional"))
    )
    (net (code "73") (name "P0.23") (class "Default")
      (node (ref "U$1") (pin "P$AC19") (pinfunction "P0.23_P$AC19") (pintype "bidirectional"))
    )
    (net (code "74") (name "P0.24") (class "Default")
      (node (ref "U$1") (pin "P$AD20") (pinfunction "P0.24_P$AD20") (pintype "bidirectional"))
    )
    (net (code "75") (name "P0.25") (class "Default")
      (node (ref "U$1") (pin "P$AC21") (pinfunction "P0.25_P$AC21") (pintype "bidirectional"))
    )
    (net (code "76") (name "P0.26") (class "Default")
      (node (ref "U$1") (pin "P$G1") (pinfunction "P0.26_P$G1") (pintype "bidirectional"))
    )
    (net (code "77") (name "P0.27") (class "Default")
      (node (ref "U$1") (pin "P$H2") (pinfunction "P0.27_P$H2") (pintype "bidirectional"))
    )
    (net (code "78") (name "P0.28") (class "Default")
      (node (ref "U$1") (pin "P$B11") (pinfunction "P0.28/AIN4_P$B11") (pintype "bidirectional"))
    )
    (net (code "79") (name "P0.29") (class "Default")
      (node (ref "U$1") (pin "P$A10") (pinfunction "P0.29/AIN5_P$A10") (pintype "bidirectional"))
    )
    (net (code "80") (name "P0.30") (class "Default")
      (node (ref "U$1") (pin "P$B9") (pinfunction "P0.30/AIN6_P$B9") (pintype "bidirectional"))
    )
    (net (code "81") (name "P0.31") (class "Default")
      (node (ref "U$1") (pin "P$A8") (pinfunction "P0.31/AIN7_P$A8") (pintype "bidirectional"))
    )
    (net (code "82") (name "P1.01{slash}1.6C") (class "Default")
      (node (ref "Q1") (pin "1") (pinfunction "G_1") (pintype "bidirectional"))
      (node (ref "R_PWR_EPD") (pin "1") (pinfunction "1_1") (pintype "bidirectional"))
    )
    (net (code "83") (name "P1.01{slash}2.4B") (class "Default")
      (node (ref "U$1") (pin "P$Y23") (pinfunction "P1.01_P$Y23") (pintype "bidirectional"))
    )
    (net (code "84") (name "P1.02{slash}1.6C") (class "Default")
      (node (ref "C29") (pin "2") (pinfunction "2_2") (pintype "passive"))
      (node (ref "R7") (pin "1") (pinfunction "1_1") (pintype "bidirectional"))
      (node (ref "SW_DN") (pin "2") (pinfunction "2_2") (pintype "passive"))
    )
    (net (code "85") (name "P1.02{slash}2.8C") (class "Default")
      (node (ref "U$1") (pin "P$W24") (pinfunction "P1.02_P$W24") (pintype "bidirectional"))
    )
    (net (code "86") (name "P1.03") (class "Default")
      (node (ref "U$1") (pin "P$V23") (pinfunction "P1.03_P$V23") (pintype "bidirectional"))
    )
    (net (code "87") (name "P1.04") (class "Default")
      (node (ref "U$1") (pin "P$U24") (pinfunction "P1.04_P$U24") (pintype "bidirectional"))
    )
    (net (code "88") (name "P1.05") (class "Default")
      (node (ref "U$1") (pin "P$T23") (pinfunction "P1.05_P$T23") (pintype "bidirectional"))
    )
    (net (code "89") (name "P1.06") (class "Default")
      (node (ref "U$1") (pin "P$R24") (pinfunction "P1.06_P$R24") (pintype "bidirectional"))
    )
    (net (code "90") (name "P1.07") (class "Default")
      (node (ref "U$1") (pin "P$P23") (pinfunction "P1.07_P$P23") (pintype "bidirectional"))
    )
    (net (code "91") (name "P1.09") (class "Default")
      (node (ref "U$1") (pin "P$R1") (pinfunction "P1.09_P$R1") (pintype "bidirectional"))
    )
    (net (code "92") (name "P1.10") (class "Default")
      (node (ref "U$1") (pin "P$A20") (pinfunction "P1.10_P$A20") (pintype "bidirectional"))
    )
    (net (code "93") (name "P1.11") (class "Default")
      (node (ref "U$1") (pin "P$B19") (pinfunction "P1.11_P$B19") (pintype "bidirectional"))
    )
    (net (code "94") (name "P1.12") (class "Default")
      (node (ref "U$1") (pin "P$B17") (pinfunction "P1.12_P$B17") (pintype "bidirectional"))
    )
    (net (code "95") (name "P1.13") (class "Default")
      (node (ref "U$1") (pin "P$A16") (pinfunction "P1.13_P$A16") (pintype "bidirectional"))
    )
    (net (code "96") (name "P1.14") (class "Default")
      (node (ref "U$1") (pin "P$B15") (pinfunction "P1.14_P$B15") (pintype "bidirectional"))
    )
    (net (code "97") (name "P1.15") (class "Default")
      (node (ref "U$1") (pin "P$A14") (pinfunction "P1.15_P$A14") (pintype "bidirectional"))
    )
    (net (code "98") (name "PMIC_INT") (class "Default")
      (node (ref "IC1") (pin "A1") (pinfunction "~{INT}_A1") (pintype "bidirectional"))
      (node (ref "U$1") (pin "P$T2") (pinfunction "P0.11_P$T2") (pintype "bidirectional"))
    )
    (net (code "99") (name "PREVGH") (class "Default")
      (node (ref "D5") (pin "1") (pinfunction "K_1") (pintype "bidirectional"))
      (node (ref "EPD_C9") (pin "2") (pinfunction "2_2") (pintype "passive"))
      (node (ref "J2") (pin "21") (pinfunction "21_21") (pintype "bidirectional"))
    )
    (net (code "100") (name "PREVGL") (class "Default")
      (node (ref "D2") (pin "2") (pinfunction "A_2") (pintype "bidirectional"))
      (node (ref "EPD_C11") (pin "2") (pinfunction "2_2") (pintype "passive"))
      (node (ref "J2") (pin "23") (pinfunction "23_23") (pintype "bidirectional"))
    )
    (net (code "101") (name "RESE") (class "Default")
      (node (ref "J2") (pin "3") (pinfunction "3_3") (pintype "bidirectional"))
      (node (ref "Q3") (pin "2") (pinfunction "S_2") (pintype "bidirectional"))
      (node (ref "R1_EP_DR") (pin "2") (pinfunction "2_2") (pintype "bidirectional"))
    )
    (net (code "102") (name "RESET") (class "Default")
      (node (ref "J1") (pin "6") (pinfunction "6_6") (pintype "bidirectional"))
      (node (ref "TP_RESET") (pin "TP") (pinfunction "TP_TP") (pintype "input"))
      (node (ref "U$1") (pin "P$AC13") (pinfunction "P0.18/RESET_P$AC13") (pintype "bidirectional"))
    )
    (net (code "103") (name "SCK{slash}1.5B") (class "Default")
      (node (ref "J2") (pin "13") (pinfunction "13_13") (pintype "bidirectional"))
    )
    (net (code "104") (name "SCK{slash}2.2D") (class "Default")
      (node (ref "U$1") (pin "P$A12") (pinfunction "P0.02/AIN0_P$A12") (pintype "bidirectional"))
    )
    (net (code "105") (name "SCL{slash}1.4C") (class "Default")
      (node (ref "IC4") (pin "C1") (pinfunction "SCL_C1") (pintype "bidirectional"))
      (node (ref "U3") (pin "7") (pinfunction "SCL_7") (pintype "input"))
      (node (ref "U3") (pin "8") (pinfunction "SDA_8") (pintype "bidirectional"))
    )
    (net (code "106") (name "SCL{slash}2.4C") (class "Default")
      (node (ref "IC1") (pin "B1") (pinfunction "SCL_B1") (pintype "bidirectional"))
      (node (ref "IC3") (pin "12") (pinfunction "SCX_12") (pintype "bidirectional"))
      (node (ref "R17") (pin "2") (pinfunction "2_2") (pintype "bidirectional"))
      (node (ref "R4") (pin "2") (pinfunction "2_2") (pintype "bidirectional"))
      (node (ref "TP_SCL") (pin "TP") (pinfunction "TP_TP") (pintype "input"))
      (node (ref "U$1") (pin "P$M2") (pinfunction "P0.07_P$M2") (pintype "bidirectional"))
    )
    (net (code "107") (name "SDA{slash}1.4C") (class "Default")
      (node (ref "IC4") (pin "B2") (pinfunction "SDA_B2") (pintype "bidirectional"))
    )
    (net (code "108") (name "SDA{slash}2.4C") (class "Default")
      (node (ref "IC1") (pin "C1") (pinfunction "SDA_C1") (pintype "bidirectional"))
      (node (ref "IC3") (pin "2") (pinfunction "SDX_2") (pintype "bidirectional"))
      (node (ref "R18") (pin "2") (pinfunction "2_2") (pintype "bidirectional"))
      (node (ref "R2") (pin "2") (pinfunction "2_2") (pintype "bidirectional"))
      (node (ref "TP_SDA") (pin "TP") (pinfunction "TP_TP") (pintype "input"))
      (node (ref "U$1") (pin "P$L1") (pinfunction "P0.06_P$L1") (pintype "bidirectional"))
    )
    (net (code "109") (name "SWDCLK") (class "Default")
      (node (ref "J1") (pin "4") (pinfunction "4_4") (pintype "bidirectional"))
      (node (ref "TP_SWDCLK") (pin "TP") (pinfunction "TP_TP") (pintype "input"))
      (node (ref "U$1") (pin "P$AA24") (pinfunction "SWDCLK_P$AA24") (pintype "input"))
    )
    (net (code "110") (name "SWDIO") (class "Default")
      (node (ref "J1") (pin "2") (pinfunction "2_2") (pintype "bidirectional"))
      (node (ref "TP_SWDIO") (pin "TP") (pinfunction "TP_TP") (pintype "input"))
      (node (ref "U$1") (pin "P$AC24") (pinfunction "SWDIO_P$AC24") (pintype "bidirectional"))
    )
    (net (code "111") (name "SWO") (class "Default")
      (node (ref "TP_SWO") (pin "TP") (pinfunction "TP_TP") (pintype "input"))
      (node (ref "U$1") (pin "P$AD22") (pinfunction "P1.00_P$AD22") (pintype "bidirectional"))
    )
    (net (code "112") (name "VBAT{slash}1.2A") (class "Default")
      (node (ref "C27") (pin "2") (pinfunction "2_2") (pintype "passive"))
      (node (ref "TP_VBAT") (pin "TP") (pinfunction "TP_TP") (pintype "input"))
      (node (ref "U3") (pin "2") (pinfunction "CELL_2") (pintype "power_in"))
      (node (ref "U3") (pin "3") (pinfunction "VDD_3") (pintype "power_in"))
    )
    (net (code "113") (name "VBAT{slash}2.5C") (class "Default")
      (node (ref "C37") (pin "2") (pinfunction "2_2") (pintype "passive"))
      (node (ref "IC1") (pin "C2") (pinfunction "BAT_C2") (pintype "bidirectional"))
    )
    (net (code "114") (name "VBUS{slash}1.5D") (class "Default")
      (node (ref "C42") (pin "1") (pinfunction "1_1") (pintype "passive"))
      (node (ref "C43") (pin "1") (pinfunction "1_1") (pintype "passive"))
      (node (ref "D3") (pin "5") (pinfunction "VBUS_5") (pintype "bidirectional"))
      (node (ref "J4") (pin "A4_B9") (pinfunction "VBUS_A4_B9") (pintype "power_in"))
      (node (ref "J4") (pin "A9_B4") (pinfunction "VBUS_A9_B4") (pintype "power_in"))
    )
    (net (code "115") (name "VBUS{slash}2.6D") (class "Default")
      (node (ref "C21") (pin "1") (pinfunction "1_1") (pintype "passive"))
      (node (ref "C38") (pin "2") (pinfunction "2_2") (pintype "passive"))
      (node (ref "IC1") (pin "A2") (pinfunction "IN_A2") (pintype "bidirectional"))
      (node (ref "U$1") (pin "P$AD2") (pinfunction "VBUS_P$AD2") (pintype "power_in"))
    )
    (net (code "116") (name "VREG") (class "Default")
      (node (ref "C23") (pin "2") (pinfunction "2_2") (pintype "passive"))
      (node (ref "C24") (pin "1") (pinfunction "1_1") (pintype "passive"))
      (node (ref "C39") (pin "1") (pinfunction "1_1") (pintype "passive"))
      (node (ref "IC1") (pin "B2") (pinfunction "SYS_B2") (pintype "bidirectional"))
      (node (ref "IC2") (pin "A1") (pinfunction "EN_A1") (pintype "bidirectional"))
      (node (ref "IC2") (pin "A2") (pinfunction "VIN_1_A2") (pintype "bidirectional"))
      (node (ref "IC2") (pin "A3") (pinfunction "VIN_2_A3") (pintype "bidirectional"))
      (node (ref "TP_VREG") (pin "TP") (pinfunction "TP_TP") (pintype "input"))
    )
    (net (code "117") (name "unconnected-(ANT1-NC-Pad2)") (class "Default")
      (node (ref "ANT1") (pin "2") (pinfunction "NC_2") (pintype "no_connect"))
    )
    (net (code "118") (name "unconnected-(IC3-ASCL-Pad11)") (class "Default")
      (node (ref "IC3") (pin "11") (pinfunction "ASCL_11") (pintype "bidirectional"))
    )
    (net (code "119") (name "unconnected-(IC3-ASDA-Pad4)") (class "Default")
      (node (ref "IC3") (pin "4") (pinfunction "ASDA_4") (pintype "bidirectional"))
    )
    (net (code "120") (name "unconnected-(J2-Pad1)") (class "Default")
      (node (ref "J2") (pin "1") (pinfunction "1_1") (pintype "bidirectional"))
    )
    (net (code "121") (name "unconnected-(J2-Pad6)") (class "Default")
      (node (ref "J2") (pin "6") (pinfunction "6_6") (pintype "bidirectional"))
    )
    (net (code "122") (name "unconnected-(J2-Pad7)") (class "Default")
      (node (ref "J2") (pin "7") (pinfunction "7_7") (pintype "bidirectional"))
    )
    (net (code "123") (name "unconnected-(J4-SBU1-PadA8)") (class "Default")
      (node (ref "J4") (pin "A8") (pinfunction "SBU1_A8") (pintype "bidirectional"))
    )
    (net (code "124") (name "unconnected-(J4-SBU2-PadB8)") (class "Default")
      (node (ref "J4") (pin "B8") (pinfunction "SBU2_B8") (pintype "bidirectional"))
    )
    (net (code "125") (name "unconnected-(U$1-DCCH-PadP$AB2)") (class "Default")
      (node (ref "U$1") (pin "P$AB2") (pinfunction "DCCH_P$AB2") (pintype "bidirectional"))
    )
  )
)
